# Electronic_Load_AD_V2A.net
KiCad netlist of a schematic drawn in EAGLE
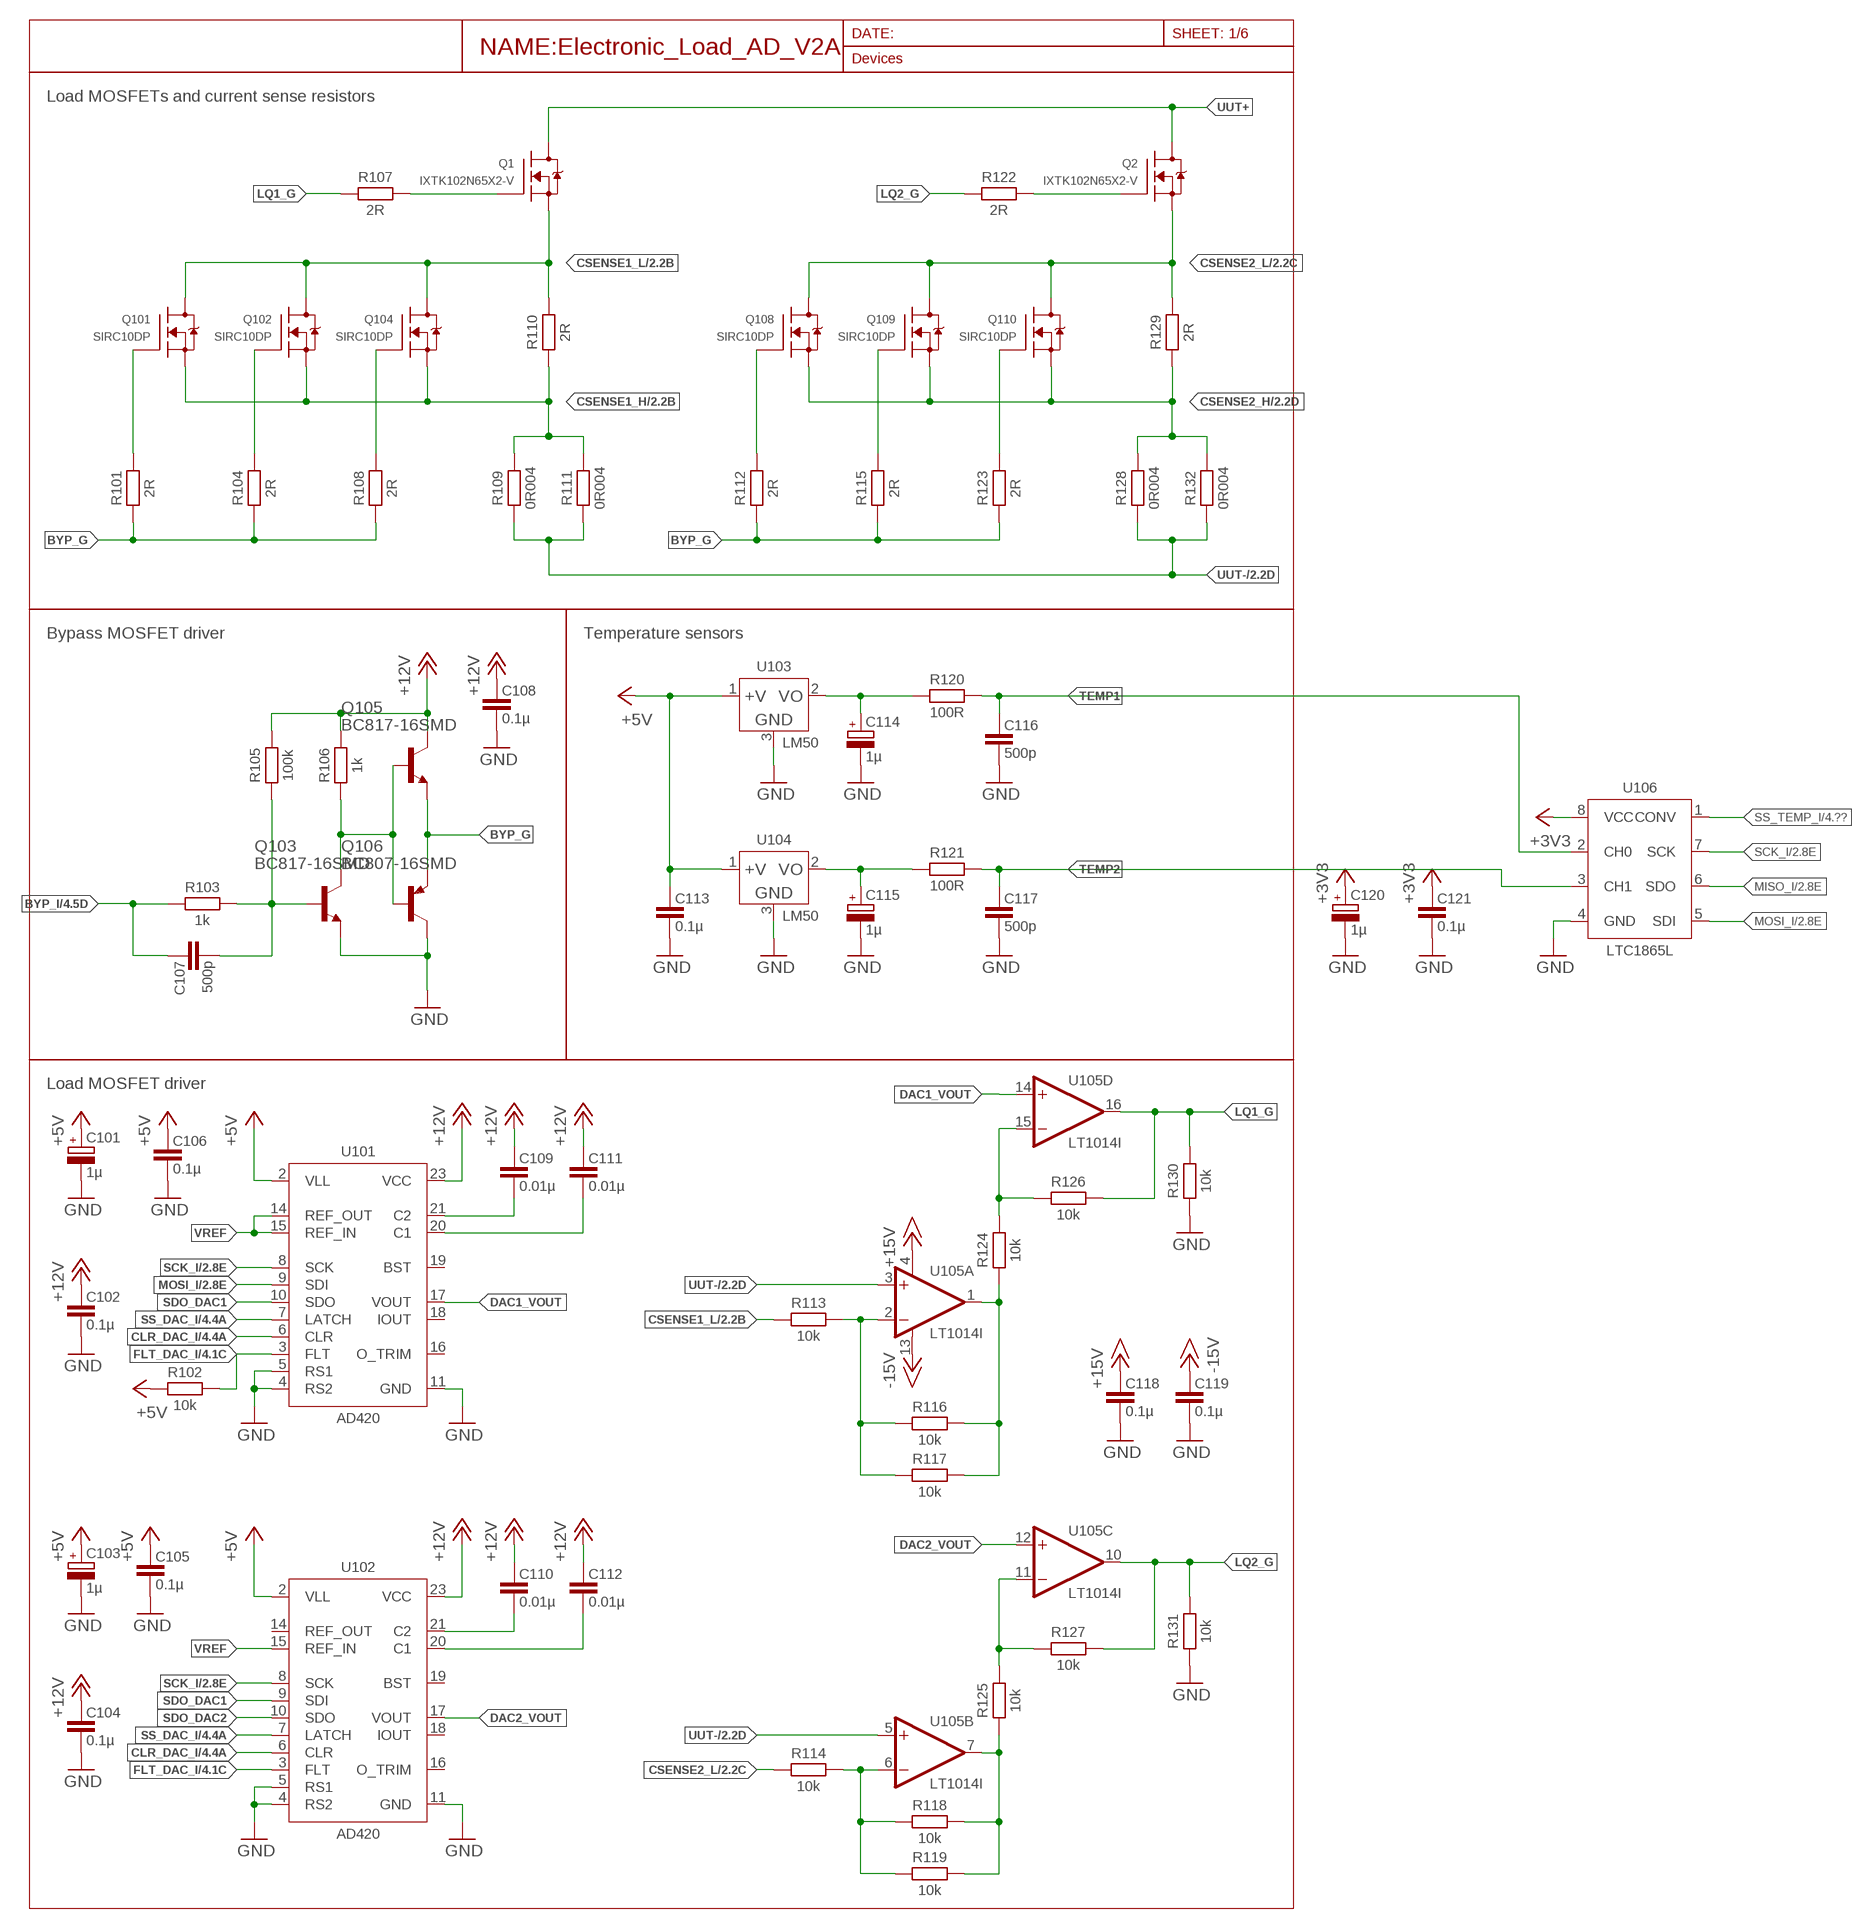
[diagram p0: schematic, sheet 1]
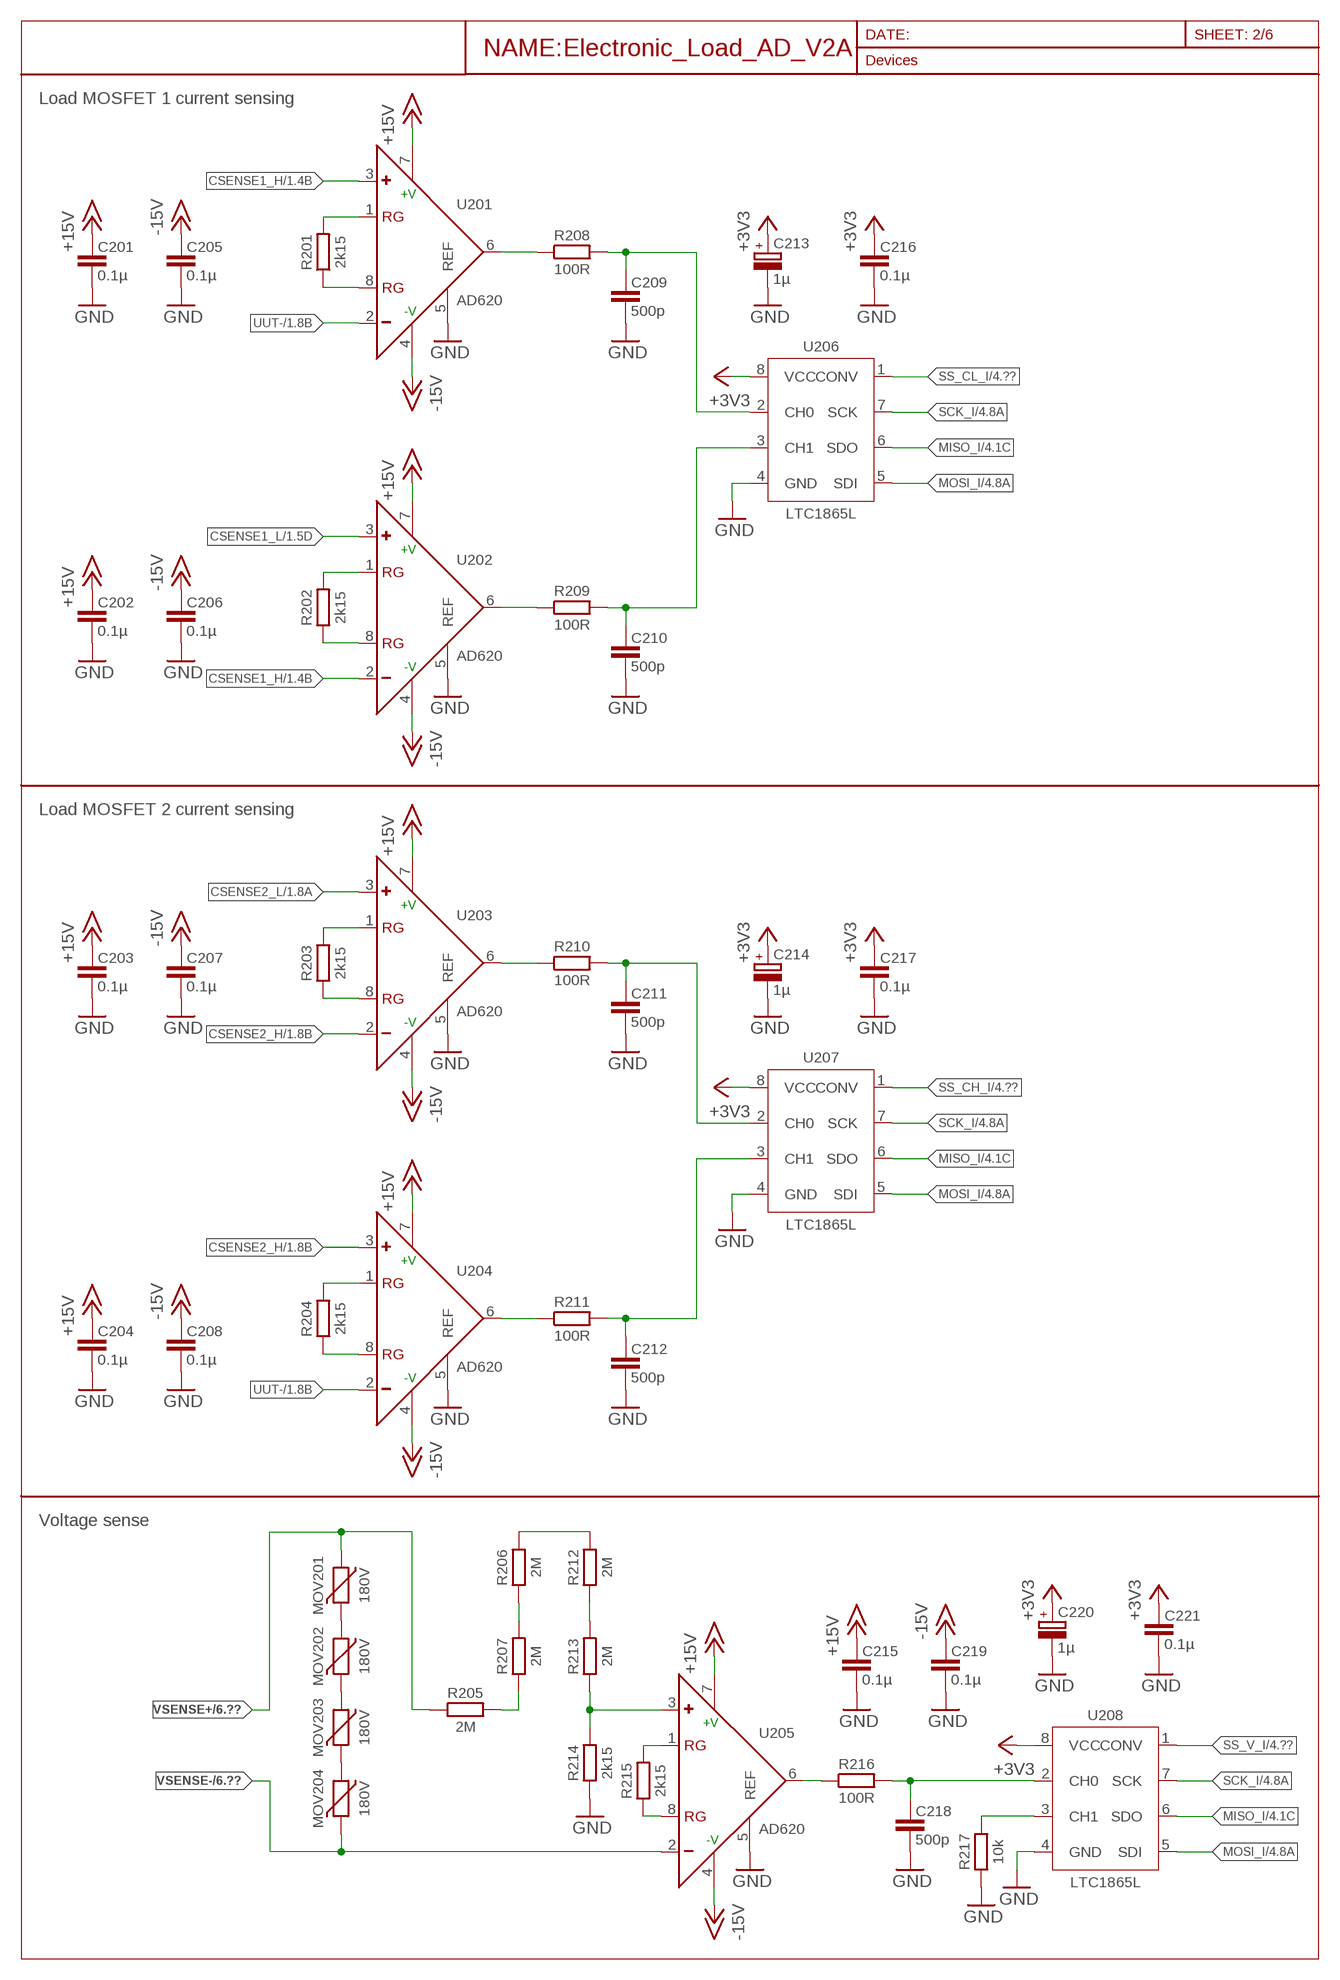
[diagram p1: schematic, sheet 2]
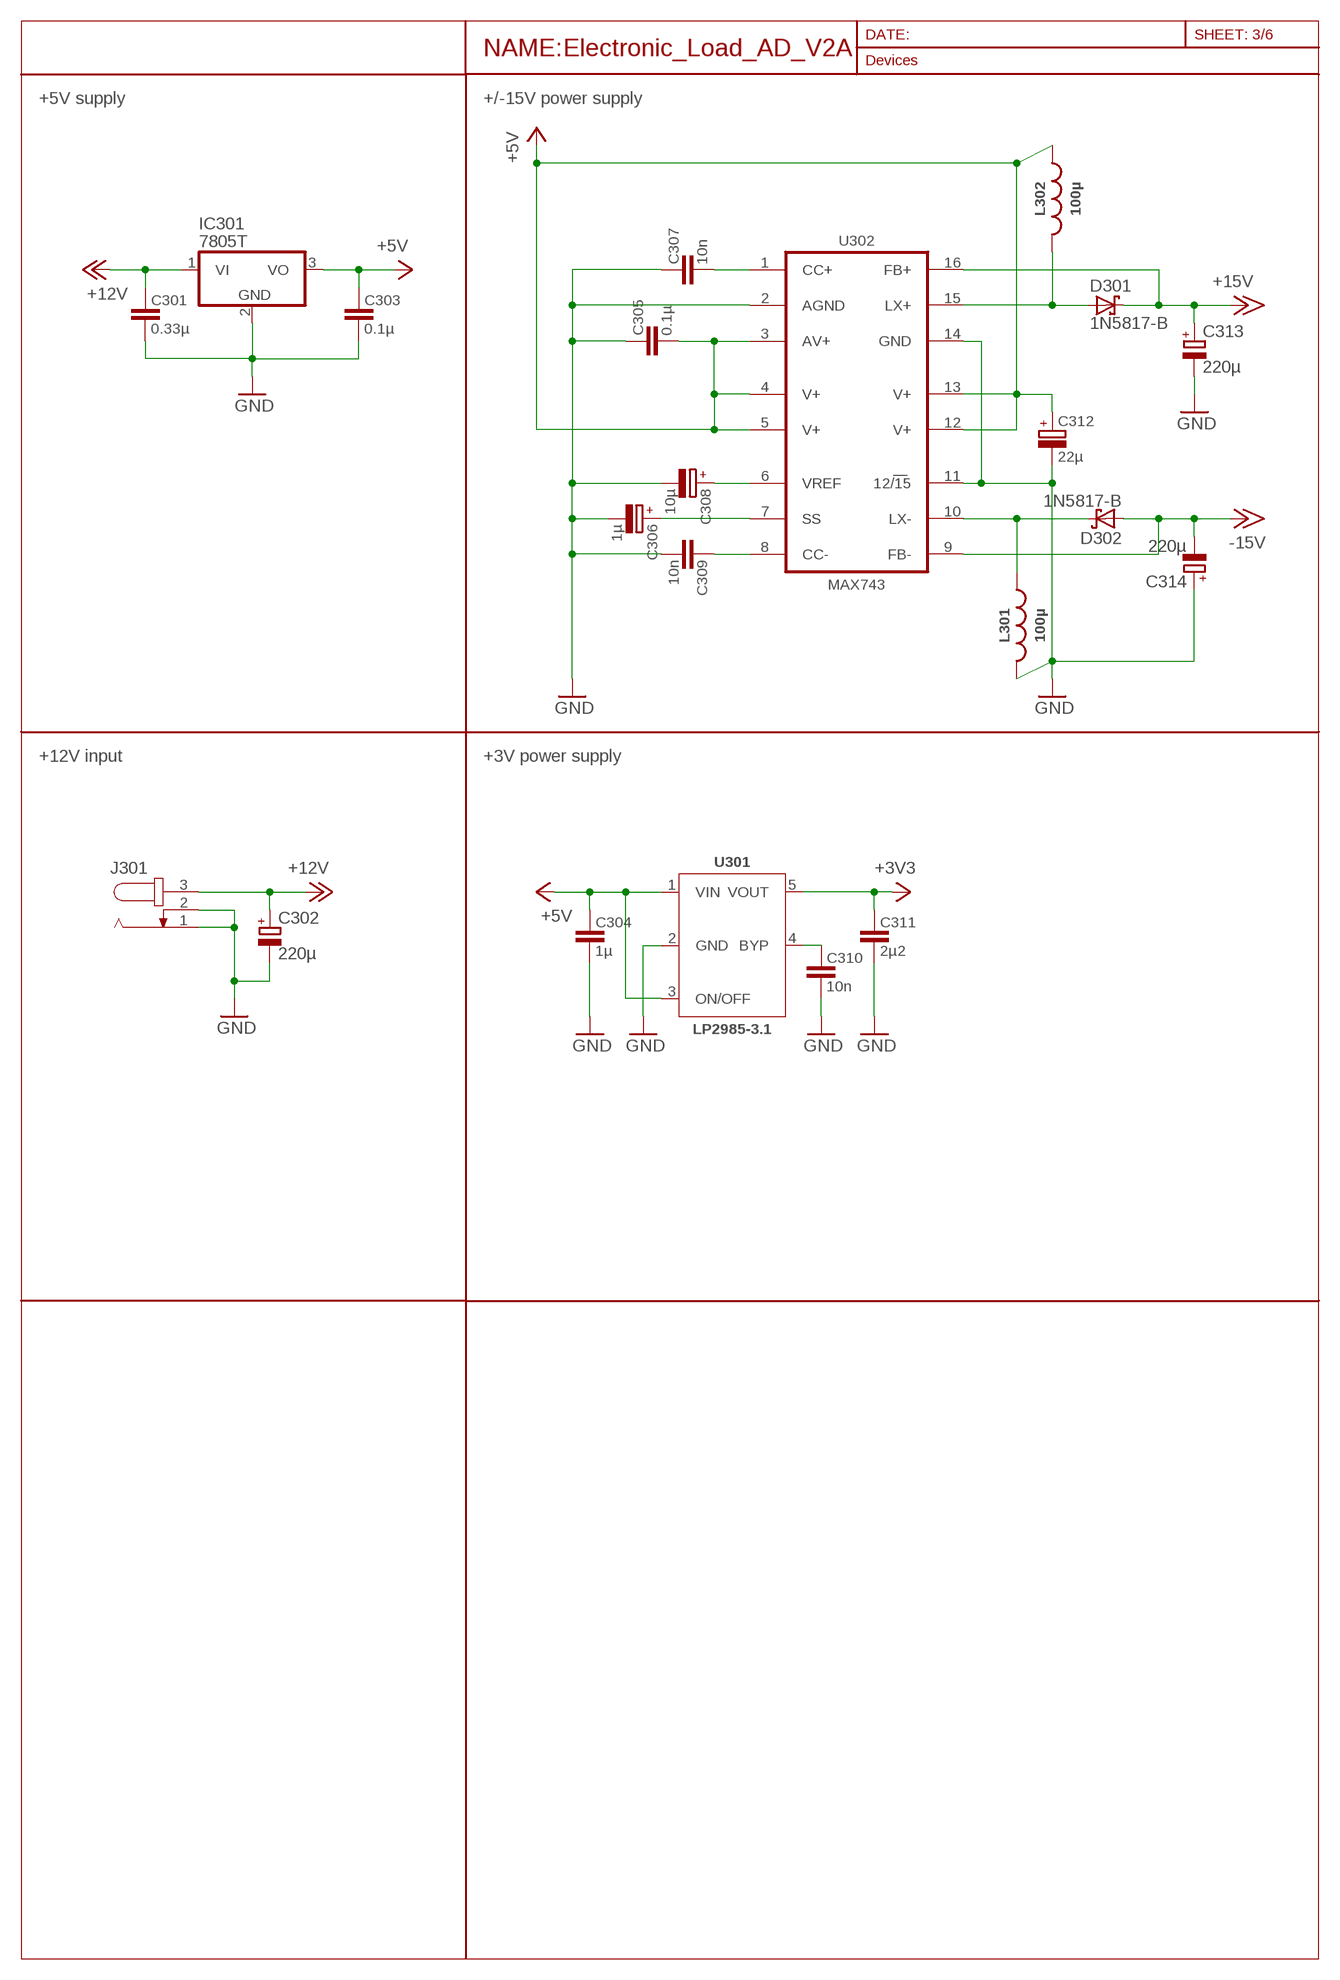
[diagram p2: schematic, sheet 3]
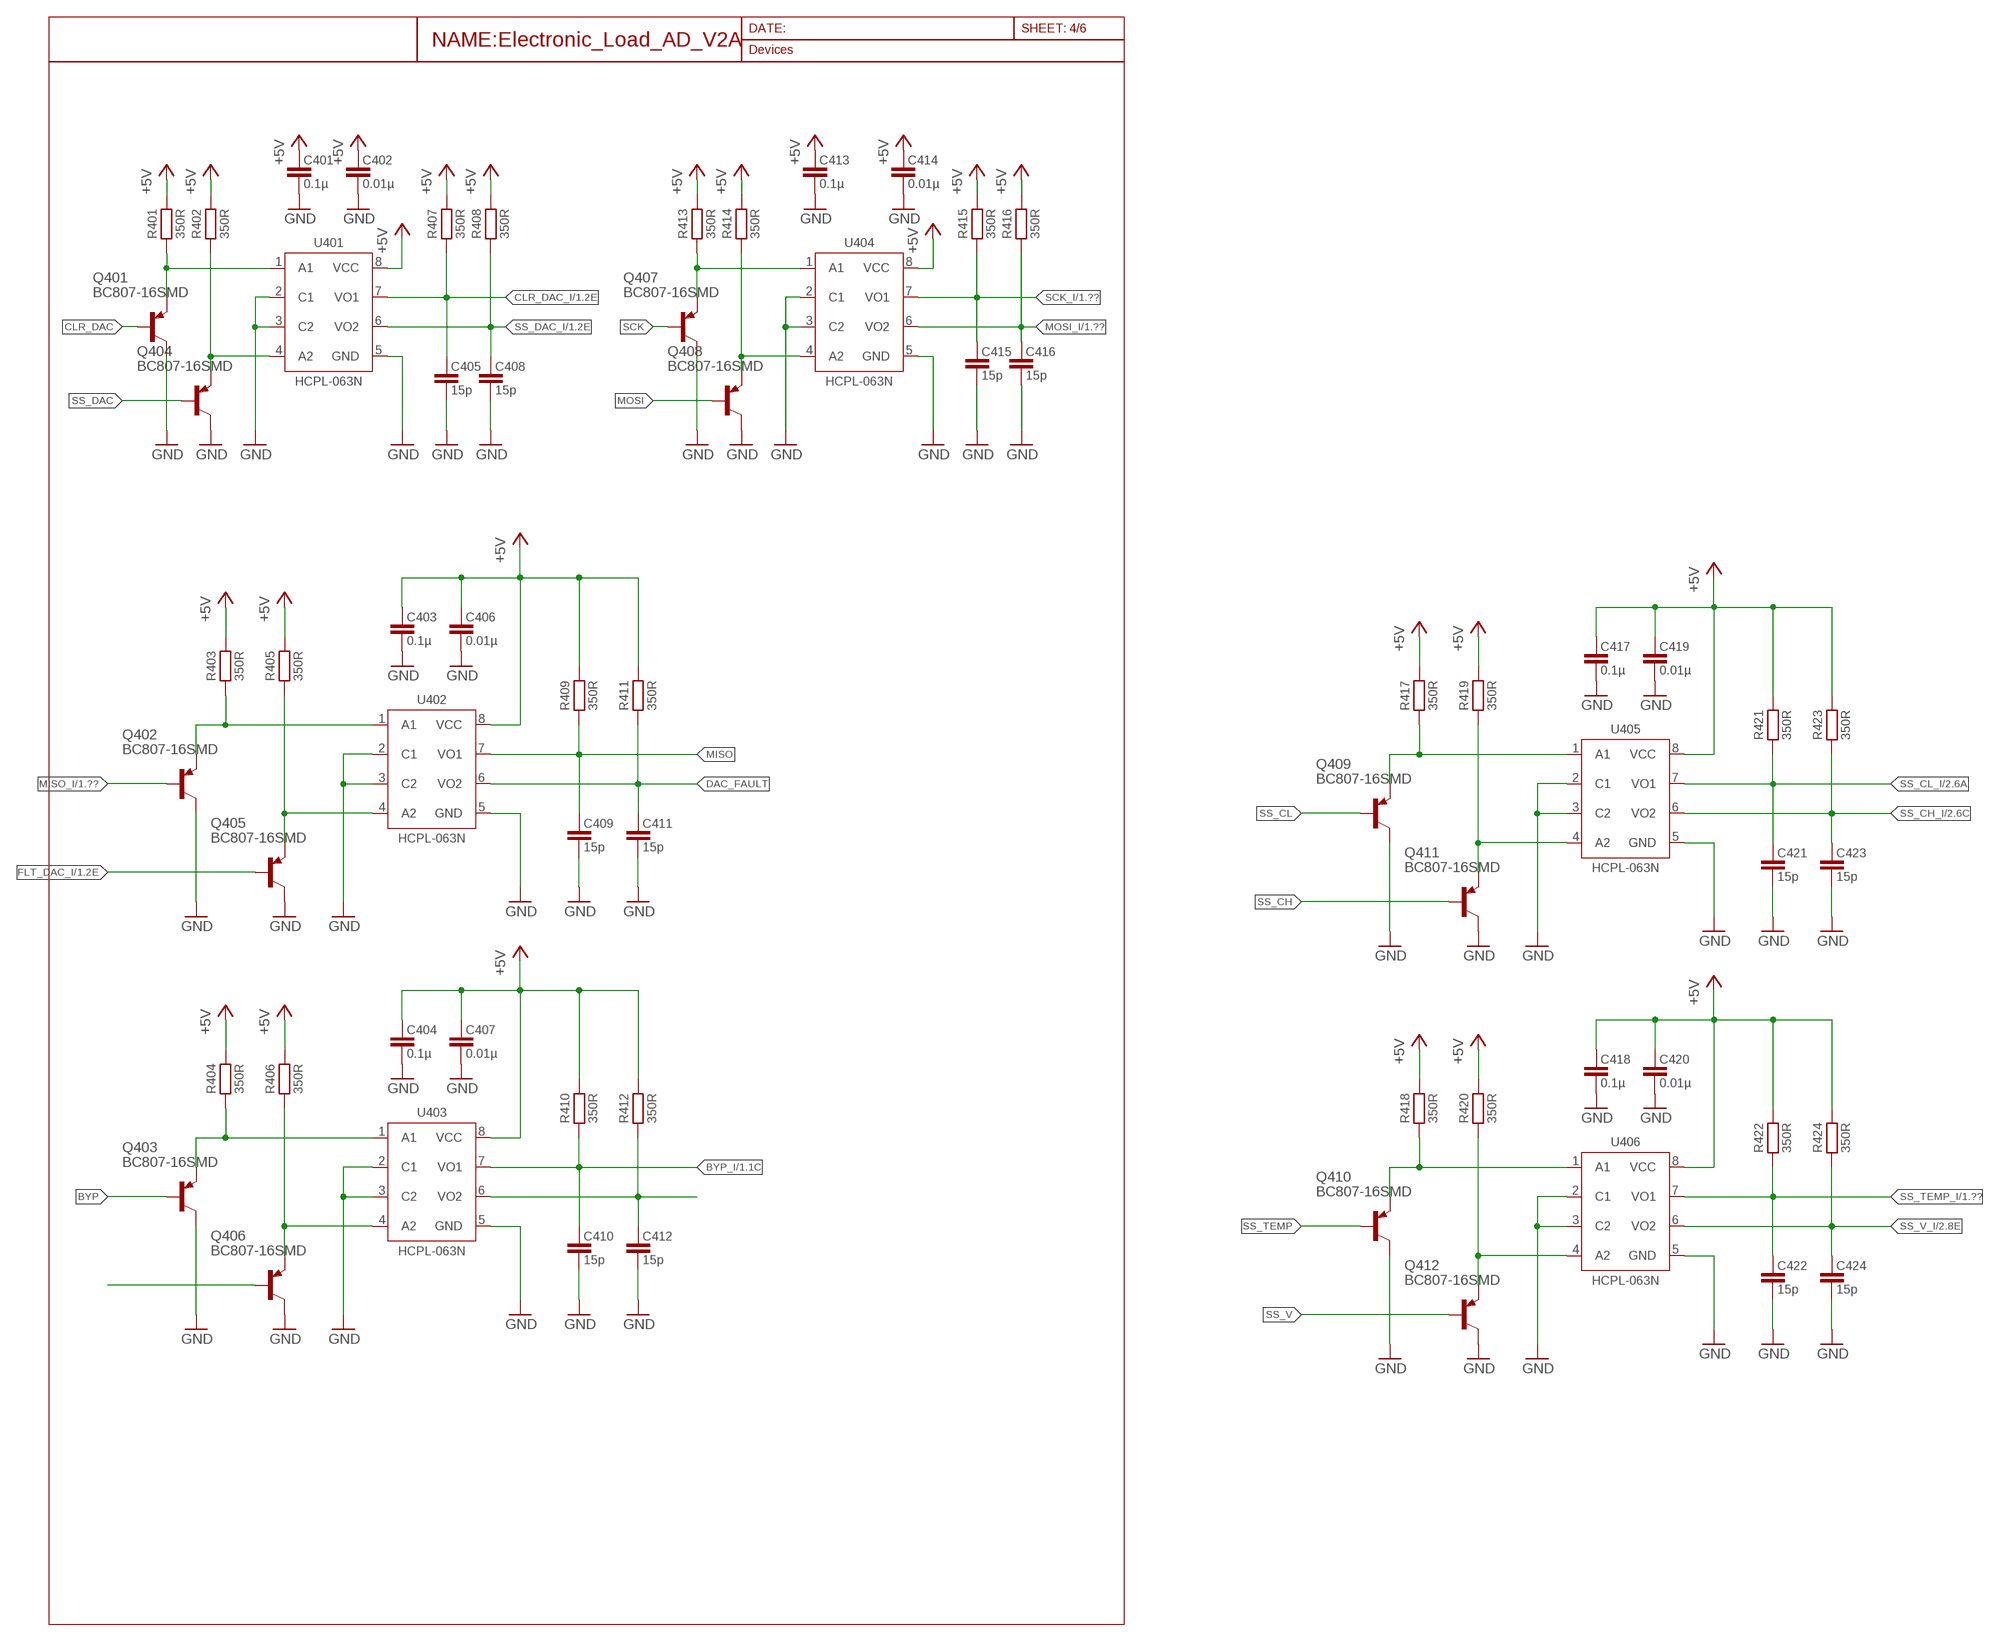
[diagram p3: schematic, sheet 4]
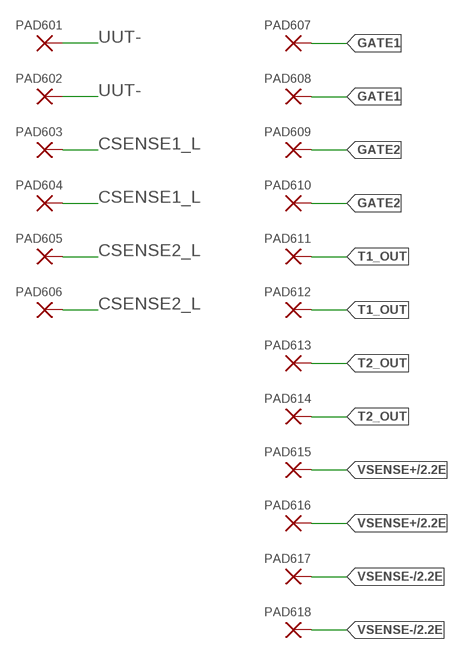
[diagram p4: schematic, sheet 6]

(export (version "E")
  (design (tool "Eeschema 10.0.6"))
  (components
    (comp (ref "C201")
      (value "0.1µ")
      (footprint "eagle-import:C3216")
      (libsource (lib "eagle-import") (part "C-EU-3216"))
    )
    (comp (ref "C202")
      (value "0.1µ")
      (footprint "eagle-import:C3216")
      (libsource (lib "eagle-import") (part "C-EU-3216"))
    )
    (comp (ref "C203")
      (value "0.1µ")
      (footprint "eagle-import:C3216")
      (libsource (lib "eagle-import") (part "C-EU-3216"))
    )
    (comp (ref "C204")
      (value "0.1µ")
      (footprint "eagle-import:C3216")
      (libsource (lib "eagle-import") (part "C-EU-3216"))
    )
    (comp (ref "C205")
      (value "0.1µ")
      (footprint "eagle-import:C3216")
      (libsource (lib "eagle-import") (part "C-EU-3216"))
    )
    (comp (ref "C206")
      (value "0.1µ")
      (footprint "eagle-import:C3216")
      (libsource (lib "eagle-import") (part "C-EU-3216"))
    )
    (comp (ref "C207")
      (value "0.1µ")
      (footprint "eagle-import:C3216")
      (libsource (lib "eagle-import") (part "C-EU-3216"))
    )
    (comp (ref "C208")
      (value "0.1µ")
      (footprint "eagle-import:C3216")
      (libsource (lib "eagle-import") (part "C-EU-3216"))
    )
    (comp (ref "C209")
      (value "500p")
      (footprint "eagle-import:C1608")
      (libsource (lib "eagle-import") (part "C-EU-1608"))
    )
    (comp (ref "C210")
      (value "500p")
      (footprint "eagle-import:C1608")
      (libsource (lib "eagle-import") (part "C-EU-1608"))
    )
    (comp (ref "C211")
      (value "500p")
      (footprint "eagle-import:C1608")
      (libsource (lib "eagle-import") (part "C-EU-1608"))
    )
    (comp (ref "C212")
      (value "500p")
      (footprint "eagle-import:C1608")
      (libsource (lib "eagle-import") (part "C-EU-1608"))
    )
    (comp (ref "C213")
      (value "1µ")
      (footprint "eagle-import:CT3216")
      (libsource (lib "eagle-import") (part "CPOL-3216-A"))
    )
    (comp (ref "C214")
      (value "1µ")
      (footprint "eagle-import:CT3216")
      (libsource (lib "eagle-import") (part "CPOL-3216-A"))
    )
    (comp (ref "C215")
      (value "0.1µ")
      (footprint "eagle-import:C3216")
      (libsource (lib "eagle-import") (part "C-EU-3216"))
    )
    (comp (ref "C216")
      (value "0.1µ")
      (footprint "eagle-import:C3216")
      (libsource (lib "eagle-import") (part "C-EU-3216"))
    )
    (comp (ref "C217")
      (value "0.1µ")
      (footprint "eagle-import:C3216")
      (libsource (lib "eagle-import") (part "C-EU-3216"))
    )
    (comp (ref "C218")
      (value "500p")
      (footprint "eagle-import:C1608")
      (libsource (lib "eagle-import") (part "C-EU-1608"))
    )
    (comp (ref "C219")
      (value "0.1µ")
      (footprint "eagle-import:C3216")
      (libsource (lib "eagle-import") (part "C-EU-3216"))
    )
    (comp (ref "C220")
      (value "1µ")
      (footprint "eagle-import:CT3216")
      (libsource (lib "eagle-import") (part "CPOL-3216-A"))
    )
    (comp (ref "C221")
      (value "0.1µ")
      (footprint "eagle-import:C3216")
      (libsource (lib "eagle-import") (part "C-EU-3216"))
    )
    (comp (ref "MOV201")
      (value "180V")
      (footprint "eagle-import:R3225W")
      (libsource (lib "eagle-import") (part "MOV-3225"))
    )
    (comp (ref "MOV202")
      (value "180V")
      (footprint "eagle-import:R3225W")
      (libsource (lib "eagle-import") (part "MOV-3225"))
    )
    (comp (ref "MOV203")
      (value "180V")
      (footprint "eagle-import:R3225W")
      (libsource (lib "eagle-import") (part "MOV-3225"))
    )
    (comp (ref "MOV204")
      (value "180V")
      (footprint "eagle-import:R3225W")
      (libsource (lib "eagle-import") (part "MOV-3225"))
    )
    (comp (ref "R201")
      (value "2k15")
      (footprint "eagle-import:R2012W")
      (libsource (lib "eagle-import") (part "R-EU-2012"))
    )
    (comp (ref "R202")
      (value "2k15")
      (footprint "eagle-import:R2012W")
      (libsource (lib "eagle-import") (part "R-EU-2012"))
    )
    (comp (ref "R203")
      (value "2k15")
      (footprint "eagle-import:R2012W")
      (libsource (lib "eagle-import") (part "R-EU-2012"))
    )
    (comp (ref "R204")
      (value "2k15")
      (footprint "eagle-import:R2012W")
      (libsource (lib "eagle-import") (part "R-EU-2012"))
    )
    (comp (ref "R205")
      (value "2M")
      (footprint "eagle-import:R3216W")
      (libsource (lib "eagle-import") (part "R-EU-3216"))
    )
    (comp (ref "R206")
      (value "2M")
      (footprint "eagle-import:R3216W")
      (libsource (lib "eagle-import") (part "R-EU-3216"))
    )
    (comp (ref "R207")
      (value "2M")
      (footprint "eagle-import:R3216W")
      (libsource (lib "eagle-import") (part "R-EU-3216"))
    )
    (comp (ref "R208")
      (value "100R")
      (footprint "eagle-import:R2012W")
      (libsource (lib "eagle-import") (part "R-EU-2012"))
    )
    (comp (ref "R209")
      (value "100R")
      (footprint "eagle-import:R2012W")
      (libsource (lib "eagle-import") (part "R-EU-2012"))
    )
    (comp (ref "R210")
      (value "100R")
      (footprint "eagle-import:R2012W")
      (libsource (lib "eagle-import") (part "R-EU-2012"))
    )
    (comp (ref "R211")
      (value "100R")
      (footprint "eagle-import:R2012W")
      (libsource (lib "eagle-import") (part "R-EU-2012"))
    )
    (comp (ref "R212")
      (value "2M")
      (footprint "eagle-import:R3216W")
      (libsource (lib "eagle-import") (part "R-EU-3216"))
    )
    (comp (ref "R213")
      (value "2M")
      (footprint "eagle-import:R3216W")
      (libsource (lib "eagle-import") (part "R-EU-3216"))
    )
    (comp (ref "R214")
      (value "2k15")
      (footprint "eagle-import:R2012W")
      (libsource (lib "eagle-import") (part "R-EU-2012"))
    )
    (comp (ref "R215")
      (value "2k15")
      (footprint "eagle-import:R2012W")
      (libsource (lib "eagle-import") (part "R-EU-2012"))
    )
    (comp (ref "R216")
      (value "100R")
      (footprint "eagle-import:R2012W")
      (libsource (lib "eagle-import") (part "R-EU-2012"))
    )
    (comp (ref "R217")
      (value "10k")
      (footprint "eagle-import:R1608")
      (libsource (lib "eagle-import") (part "R-EU-1608"))
    )
    (comp (ref "U201")
      (value "AD620")
      (footprint "eagle-import:SO8")
      (libsource (lib "eagle-import") (part "AD620R-8"))
    )
    (comp (ref "U202")
      (value "AD620")
      (footprint "eagle-import:SO8")
      (libsource (lib "eagle-import") (part "AD620R-8"))
    )
    (comp (ref "U203")
      (value "AD620")
      (footprint "eagle-import:SO8")
      (libsource (lib "eagle-import") (part "AD620R-8"))
    )
    (comp (ref "U204")
      (value "AD620")
      (footprint "eagle-import:SO8")
      (libsource (lib "eagle-import") (part "AD620R-8"))
    )
    (comp (ref "U205")
      (value "AD620")
      (footprint "eagle-import:SO8")
      (libsource (lib "eagle-import") (part "AD620R-8"))
    )
    (comp (ref "U206")
      (value "LTC1865L")
      (footprint "eagle-import:SO8")
      (libsource (lib "eagle-import") (part "LTC1865L"))
    )
    (comp (ref "U207")
      (value "LTC1865L")
      (footprint "eagle-import:SO8")
      (libsource (lib "eagle-import") (part "LTC1865L"))
    )
    (comp (ref "U208")
      (value "LTC1865L")
      (footprint "eagle-import:SO8")
      (libsource (lib "eagle-import") (part "LTC1865L"))
    )
    (comp (ref "C301")
      (value "0.33µ")
      (footprint "eagle-import:C3216")
      (libsource (lib "eagle-import") (part "C-EU-3216"))
    )
    (comp (ref "C302")
      (value "220µ")
      (footprint "eagle-import:E3,5-10")
      (libsource (lib "eagle-import") (part "CPOL-EUE3.5-10"))
    )
    (comp (ref "C303")
      (value "0.1µ")
      (footprint "eagle-import:C3216")
      (libsource (lib "eagle-import") (part "C-EU-3216"))
    )
    (comp (ref "C304")
      (value "1µ")
      (footprint "eagle-import:C3216")
      (libsource (lib "eagle-import") (part "C-EU-3216"))
    )
    (comp (ref "C305")
      (value "0.1µ")
      (footprint "eagle-import:C3216")
      (libsource (lib "eagle-import") (part "C-EU-3216"))
    )
    (comp (ref "C306")
      (value "1µ")
      (footprint "eagle-import:CT3216")
      (libsource (lib "eagle-import") (part "CPOL-3216-A"))
    )
    (comp (ref "C307")
      (value "10n")
      (footprint "eagle-import:C3216")
      (libsource (lib "eagle-import") (part "C-EU-3216"))
    )
    (comp (ref "C308")
      (value "10µ")
      (footprint "eagle-import:CT6032")
      (libsource (lib "eagle-import") (part "CPOL-6032-C"))
    )
    (comp (ref "C309")
      (value "10n")
      (footprint "eagle-import:C3216")
      (libsource (lib "eagle-import") (part "C-EU-3216"))
    )
    (comp (ref "C310")
      (value "10n")
      (footprint "eagle-import:C3216")
      (libsource (lib "eagle-import") (part "C-EU-3216"))
    )
    (comp (ref "C311")
      (value "2µ2")
      (footprint "eagle-import:C3216")
      (libsource (lib "eagle-import") (part "C-EU-3216"))
    )
    (comp (ref "C312")
      (value "22µ")
      (footprint "eagle-import:CT6032")
      (libsource (lib "eagle-import") (part "CPOL-6032-C"))
    )
    (comp (ref "C313")
      (value "220µ")
      (footprint "eagle-import:E3,5-10")
      (libsource (lib "eagle-import") (part "CPOL-EUE3.5-10"))
    )
    (comp (ref "C314")
      (value "220µ")
      (footprint "eagle-import:E3,5-10")
      (libsource (lib "eagle-import") (part "CPOL-EUE3.5-10"))
    )
    (comp (ref "D301")
      (value "1N5817-B")
      (footprint "eagle-import:DO41-7.6")
      (libsource (lib "eagle-import") (part "1N5817-B"))
    )
    (comp (ref "D302")
      (value "1N5817-B")
      (footprint "eagle-import:DO41-7.6")
      (libsource (lib "eagle-import") (part "1N5817-B"))
    )
    (comp (ref "IC301")
      (value "7805T")
      (footprint "eagle-import:TO220H")
      (libsource (lib "eagle-import") (part "78T05"))
    )
    (comp (ref "J301")
      (value "JACK-PLUG0")
      (footprint "eagle-import:SPC4077")
      (libsource (lib "eagle-import") (part "JACK-PLUG0"))
    )
    (comp (ref "L301")
      (value "100µ")
      (footprint "eagle-import:SRN1060")
      (libsource (lib "eagle-import") (part "L-EUSRN1060"))
    )
    (comp (ref "L302")
      (value "100µ")
      (footprint "eagle-import:SRN1060")
      (libsource (lib "eagle-import") (part "L-EUSRN1060"))
    )
    (comp (ref "U301")
      (value "LP2985-3.1")
      (footprint "eagle-import:SOT23-5L")
      (libsource (lib "eagle-import") (part "LP2985-3.1"))
    )
    (comp (ref "U302")
      (value "MAX743")
      (footprint "eagle-import:SO16W")
      (libsource (lib "eagle-import") (part "MAX743WE"))
    )
    (comp (ref "C401")
      (value "0.1µ")
      (footprint "eagle-import:C3216")
      (libsource (lib "eagle-import") (part "C-EU-3216"))
    )
    (comp (ref "C402")
      (value "0.01µ")
      (footprint "eagle-import:C3216")
      (libsource (lib "eagle-import") (part "C-EU-3216"))
    )
    (comp (ref "C403")
      (value "0.1µ")
      (footprint "eagle-import:C3216")
      (libsource (lib "eagle-import") (part "C-EU-3216"))
    )
    (comp (ref "C404")
      (value "0.1µ")
      (footprint "eagle-import:C3216")
      (libsource (lib "eagle-import") (part "C-EU-3216"))
    )
    (comp (ref "C405")
      (value "15p")
      (footprint "eagle-import:C1608")
      (libsource (lib "eagle-import") (part "C-EU-1608"))
    )
    (comp (ref "C406")
      (value "0.01µ")
      (footprint "eagle-import:C3216")
      (libsource (lib "eagle-import") (part "C-EU-3216"))
    )
    (comp (ref "C407")
      (value "0.01µ")
      (footprint "eagle-import:C3216")
      (libsource (lib "eagle-import") (part "C-EU-3216"))
    )
    (comp (ref "C408")
      (value "15p")
      (footprint "eagle-import:C1608")
      (libsource (lib "eagle-import") (part "C-EU-1608"))
    )
    (comp (ref "C409")
      (value "15p")
      (footprint "eagle-import:C1608")
      (libsource (lib "eagle-import") (part "C-EU-1608"))
    )
    (comp (ref "C410")
      (value "15p")
      (footprint "eagle-import:C1608")
      (libsource (lib "eagle-import") (part "C-EU-1608"))
    )
    (comp (ref "C411")
      (value "15p")
      (footprint "eagle-import:C1608")
      (libsource (lib "eagle-import") (part "C-EU-1608"))
    )
    (comp (ref "C412")
      (value "15p")
      (footprint "eagle-import:C1608")
      (libsource (lib "eagle-import") (part "C-EU-1608"))
    )
    (comp (ref "C413")
      (value "0.1µ")
      (footprint "eagle-import:C3216")
      (libsource (lib "eagle-import") (part "C-EU-3216"))
    )
    (comp (ref "C414")
      (value "0.01µ")
      (footprint "eagle-import:C3216")
      (libsource (lib "eagle-import") (part "C-EU-3216"))
    )
    (comp (ref "C415")
      (value "15p")
      (footprint "eagle-import:C1608")
      (libsource (lib "eagle-import") (part "C-EU-1608"))
    )
    (comp (ref "C416")
      (value "15p")
      (footprint "eagle-import:C1608")
      (libsource (lib "eagle-import") (part "C-EU-1608"))
    )
    (comp (ref "C417")
      (value "0.1µ")
      (footprint "eagle-import:C3216")
      (libsource (lib "eagle-import") (part "C-EU-3216"))
    )
    (comp (ref "C418")
      (value "0.1µ")
      (footprint "eagle-import:C3216")
      (libsource (lib "eagle-import") (part "C-EU-3216"))
    )
    (comp (ref "C419")
      (value "0.01µ")
      (footprint "eagle-import:C3216")
      (libsource (lib "eagle-import") (part "C-EU-3216"))
    )
    (comp (ref "C420")
      (value "0.01µ")
      (footprint "eagle-import:C3216")
      (libsource (lib "eagle-import") (part "C-EU-3216"))
    )
    (comp (ref "C421")
      (value "15p")
      (footprint "eagle-import:C1608")
      (libsource (lib "eagle-import") (part "C-EU-1608"))
    )
    (comp (ref "C422")
      (value "15p")
      (footprint "eagle-import:C1608")
      (libsource (lib "eagle-import") (part "C-EU-1608"))
    )
    (comp (ref "C423")
      (value "15p")
      (footprint "eagle-import:C1608")
      (libsource (lib "eagle-import") (part "C-EU-1608"))
    )
    (comp (ref "C424")
      (value "15p")
      (footprint "eagle-import:C1608")
      (libsource (lib "eagle-import") (part "C-EU-1608"))
    )
    (comp (ref "Q401")
      (value "BC807-16SMD")
      (footprint "eagle-import:SOT23-BEC")
      (libsource (lib "eagle-import") (part "BC807SMD-16"))
    )
    (comp (ref "Q402")
      (value "BC807-16SMD")
      (footprint "eagle-import:SOT23-BEC")
      (libsource (lib "eagle-import") (part "BC807SMD-16"))
    )
    (comp (ref "Q403")
      (value "BC807-16SMD")
      (footprint "eagle-import:SOT23-BEC")
      (libsource (lib "eagle-import") (part "BC807SMD-16"))
    )
    (comp (ref "Q404")
      (value "BC807-16SMD")
      (footprint "eagle-import:SOT23-BEC")
      (libsource (lib "eagle-import") (part "BC807SMD-16"))
    )
    (comp (ref "Q405")
      (value "BC807-16SMD")
      (footprint "eagle-import:SOT23-BEC")
      (libsource (lib "eagle-import") (part "BC807SMD-16"))
    )
    (comp (ref "Q406")
      (value "BC807-16SMD")
      (footprint "eagle-import:SOT23-BEC")
      (libsource (lib "eagle-import") (part "BC807SMD-16"))
    )
    (comp (ref "Q407")
      (value "BC807-16SMD")
      (footprint "eagle-import:SOT23-BEC")
      (libsource (lib "eagle-import") (part "BC807SMD-16"))
    )
    (comp (ref "Q408")
      (value "BC807-16SMD")
      (footprint "eagle-import:SOT23-BEC")
      (libsource (lib "eagle-import") (part "BC807SMD-16"))
    )
    (comp (ref "Q409")
      (value "BC807-16SMD")
      (footprint "eagle-import:SOT23-BEC")
      (libsource (lib "eagle-import") (part "BC807SMD-16"))
    )
    (comp (ref "Q410")
      (value "BC807-16SMD")
      (footprint "eagle-import:SOT23-BEC")
      (libsource (lib "eagle-import") (part "BC807SMD-16"))
    )
    (comp (ref "Q411")
      (value "BC807-16SMD")
      (footprint "eagle-import:SOT23-BEC")
      (libsource (lib "eagle-import") (part "BC807SMD-16"))
    )
    (comp (ref "Q412")
      (value "BC807-16SMD")
      (footprint "eagle-import:SOT23-BEC")
      (libsource (lib "eagle-import") (part "BC807SMD-16"))
    )
    (comp (ref "R401")
      (value "350R")
      (footprint "eagle-import:R1608")
      (libsource (lib "eagle-import") (part "R-EU-1608"))
    )
    (comp (ref "R402")
      (value "350R")
      (footprint "eagle-import:R1608")
      (libsource (lib "eagle-import") (part "R-EU-1608"))
    )
    (comp (ref "R403")
      (value "350R")
      (footprint "eagle-import:R1608")
      (libsource (lib "eagle-import") (part "R-EU-1608"))
    )
    (comp (ref "R404")
      (value "350R")
      (footprint "eagle-import:R1608")
      (libsource (lib "eagle-import") (part "R-EU-1608"))
    )
    (comp (ref "R405")
      (value "350R")
      (footprint "eagle-import:R1608")
      (libsource (lib "eagle-import") (part "R-EU-1608"))
    )
    (comp (ref "R406")
      (value "350R")
      (footprint "eagle-import:R1608")
      (libsource (lib "eagle-import") (part "R-EU-1608"))
    )
    (comp (ref "R407")
      (value "350R")
      (footprint "eagle-import:R1608")
      (libsource (lib "eagle-import") (part "R-EU-1608"))
    )
    (comp (ref "R408")
      (value "350R")
      (footprint "eagle-import:R1608")
      (libsource (lib "eagle-import") (part "R-EU-1608"))
    )
    (comp (ref "R409")
      (value "350R")
      (footprint "eagle-import:R1608")
      (libsource (lib "eagle-import") (part "R-EU-1608"))
    )
    (comp (ref "R410")
      (value "350R")
      (footprint "eagle-import:R1608")
      (libsource (lib "eagle-import") (part "R-EU-1608"))
    )
    (comp (ref "R411")
      (value "350R")
      (footprint "eagle-import:R1608")
      (libsource (lib "eagle-import") (part "R-EU-1608"))
    )
    (comp (ref "R412")
      (value "350R")
      (footprint "eagle-import:R1608")
      (libsource (lib "eagle-import") (part "R-EU-1608"))
    )
    (comp (ref "R413")
      (value "350R")
      (footprint "eagle-import:R1608")
      (libsource (lib "eagle-import") (part "R-EU-1608"))
    )
    (comp (ref "R414")
      (value "350R")
      (footprint "eagle-import:R1608")
      (libsource (lib "eagle-import") (part "R-EU-1608"))
    )
    (comp (ref "R415")
      (value "350R")
      (footprint "eagle-import:R1608")
      (libsource (lib "eagle-import") (part "R-EU-1608"))
    )
    (comp (ref "R416")
      (value "350R")
      (footprint "eagle-import:R1608")
      (libsource (lib "eagle-import") (part "R-EU-1608"))
    )
    (comp (ref "R417")
      (value "350R")
      (footprint "eagle-import:R1608")
      (libsource (lib "eagle-import") (part "R-EU-1608"))
    )
    (comp (ref "R418")
      (value "350R")
      (footprint "eagle-import:R1608")
      (libsource (lib "eagle-import") (part "R-EU-1608"))
    )
    (comp (ref "R419")
      (value "350R")
      (footprint "eagle-import:R1608")
      (libsource (lib "eagle-import") (part "R-EU-1608"))
    )
    (comp (ref "R420")
      (value "350R")
      (footprint "eagle-import:R1608")
      (libsource (lib "eagle-import") (part "R-EU-1608"))
    )
    (comp (ref "R421")
      (value "350R")
      (footprint "eagle-import:R1608")
      (libsource (lib "eagle-import") (part "R-EU-1608"))
    )
    (comp (ref "R422")
      (value "350R")
      (footprint "eagle-import:R1608")
      (libsource (lib "eagle-import") (part "R-EU-1608"))
    )
    (comp (ref "R423")
      (value "350R")
      (footprint "eagle-import:R1608")
      (libsource (lib "eagle-import") (part "R-EU-1608"))
    )
    (comp (ref "R424")
      (value "350R")
      (footprint "eagle-import:R1608")
      (libsource (lib "eagle-import") (part "R-EU-1608"))
    )
    (comp (ref "U401")
      (value "HCPL-063N")
      (footprint "eagle-import:SO8")
      (libsource (lib "eagle-import") (part "HCPL-063N"))
    )
    (comp (ref "U402")
      (value "HCPL-063N")
      (footprint "eagle-import:SO8")
      (libsource (lib "eagle-import") (part "HCPL-063N"))
    )
    (comp (ref "U403")
      (value "HCPL-063N")
      (footprint "eagle-import:SO8")
      (libsource (lib "eagle-import") (part "HCPL-063N"))
    )
    (comp (ref "U404")
      (value "HCPL-063N")
      (footprint "eagle-import:SO8")
      (libsource (lib "eagle-import") (part "HCPL-063N"))
    )
    (comp (ref "U405")
      (value "HCPL-063N")
      (footprint "eagle-import:SO8")
      (libsource (lib "eagle-import") (part "HCPL-063N"))
    )
    (comp (ref "U406")
      (value "HCPL-063N")
      (footprint "eagle-import:SO8")
      (libsource (lib "eagle-import") (part "HCPL-063N"))
    )
    (comp (ref "PAD601")
      (value "PAD-10X4")
      (footprint "eagle-import:PAD-10X4")
      (libsource (lib "eagle-import") (part "PAD-10X4"))
    )
    (comp (ref "PAD602")
      (value "PAD-10X4")
      (footprint "eagle-import:PAD-10X4")
      (libsource (lib "eagle-import") (part "PAD-10X4"))
    )
    (comp (ref "PAD603")
      (value "PAD-10X4")
      (footprint "eagle-import:PAD-10X4")
      (libsource (lib "eagle-import") (part "PAD-10X4"))
    )
    (comp (ref "PAD604")
      (value "PAD-10X4")
      (footprint "eagle-import:PAD-10X4")
      (libsource (lib "eagle-import") (part "PAD-10X4"))
    )
    (comp (ref "PAD605")
      (value "PAD-10X4")
      (footprint "eagle-import:PAD-10X4")
      (libsource (lib "eagle-import") (part "PAD-10X4"))
    )
    (comp (ref "PAD606")
      (value "PAD-10X4")
      (footprint "eagle-import:PAD-10X4")
      (libsource (lib "eagle-import") (part "PAD-10X4"))
    )
    (comp (ref "PAD607")
      (value "PAD-5X2")
      (footprint "eagle-import:PAD-5X2")
      (libsource (lib "eagle-import") (part "PAD-5X2"))
    )
    (comp (ref "PAD608")
      (value "PAD-5X2")
      (footprint "eagle-import:PAD-5X2")
      (libsource (lib "eagle-import") (part "PAD-5X2"))
    )
    (comp (ref "PAD609")
      (value "PAD-5X2")
      (footprint "eagle-import:PAD-5X2")
      (libsource (lib "eagle-import") (part "PAD-5X2"))
    )
    (comp (ref "PAD610")
      (value "PAD-5X2")
      (footprint "eagle-import:PAD-5X2")
      (libsource (lib "eagle-import") (part "PAD-5X2"))
    )
    (comp (ref "PAD611")
      (value "PAD-5X2")
      (footprint "eagle-import:PAD-5X2")
      (libsource (lib "eagle-import") (part "PAD-5X2"))
    )
    (comp (ref "PAD612")
      (value "PAD-5X2")
      (footprint "eagle-import:PAD-5X2")
      (libsource (lib "eagle-import") (part "PAD-5X2"))
    )
    (comp (ref "PAD613")
      (value "PAD-5X2")
      (footprint "eagle-import:PAD-5X2")
      (libsource (lib "eagle-import") (part "PAD-5X2"))
    )
    (comp (ref "PAD614")
      (value "PAD-5X2")
      (footprint "eagle-import:PAD-5X2")
      (libsource (lib "eagle-import") (part "PAD-5X2"))
    )
    (comp (ref "PAD615")
      (value "PAD-5X2")
      (footprint "eagle-import:PAD-5X2")
      (libsource (lib "eagle-import") (part "PAD-5X2"))
    )
    (comp (ref "PAD616")
      (value "PAD-5X2")
      (footprint "eagle-import:PAD-5X2")
      (libsource (lib "eagle-import") (part "PAD-5X2"))
    )
    (comp (ref "PAD617")
      (value "PAD-5X2")
      (footprint "eagle-import:PAD-5X2")
      (libsource (lib "eagle-import") (part "PAD-5X2"))
    )
    (comp (ref "PAD618")
      (value "PAD-5X2")
      (footprint "eagle-import:PAD-5X2")
      (libsource (lib "eagle-import") (part "PAD-5X2"))
    )
    (comp (ref "C101")
      (value "1µ")
      (footprint "eagle-import:CT3216")
      (libsource (lib "eagle-import") (part "CPOL-3216-A"))
    )
    (comp (ref "C102")
      (value "0.1µ")
      (footprint "eagle-import:C3216")
      (libsource (lib "eagle-import") (part "C-EU-3216"))
    )
    (comp (ref "C103")
      (value "1µ")
      (footprint "eagle-import:CT3216")
      (libsource (lib "eagle-import") (part "CPOL-3216-A"))
    )
    (comp (ref "C104")
      (value "0.1µ")
      (footprint "eagle-import:C3216")
      (libsource (lib "eagle-import") (part "C-EU-3216"))
    )
    (comp (ref "C105")
      (value "0.1µ")
      (footprint "eagle-import:C3216")
      (libsource (lib "eagle-import") (part "C-EU-3216"))
    )
    (comp (ref "C106")
      (value "0.1µ")
      (footprint "eagle-import:C3216")
      (libsource (lib "eagle-import") (part "C-EU-3216"))
    )
    (comp (ref "C107")
      (value "500p")
      (footprint "eagle-import:C1608")
      (libsource (lib "eagle-import") (part "C-EU-1608"))
    )
    (comp (ref "C108")
      (value "0.1µ")
      (footprint "eagle-import:C3216")
      (libsource (lib "eagle-import") (part "C-EU-3216"))
    )
    (comp (ref "C109")
      (value "0.01µ")
      (footprint "eagle-import:C3216")
      (libsource (lib "eagle-import") (part "C-EU-3216"))
    )
    (comp (ref "C110")
      (value "0.01µ")
      (footprint "eagle-import:C3216")
      (libsource (lib "eagle-import") (part "C-EU-3216"))
    )
    (comp (ref "C111")
      (value "0.01µ")
      (footprint "eagle-import:C3216")
      (libsource (lib "eagle-import") (part "C-EU-3216"))
    )
    (comp (ref "C112")
      (value "0.01µ")
      (footprint "eagle-import:C3216")
      (libsource (lib "eagle-import") (part "C-EU-3216"))
    )
    (comp (ref "C113")
      (value "0.1µ")
      (footprint "eagle-import:C3216")
      (libsource (lib "eagle-import") (part "C-EU-3216"))
    )
    (comp (ref "C114")
      (value "1µ")
      (footprint "eagle-import:CT3216")
      (libsource (lib "eagle-import") (part "CPOL-3216-A"))
    )
    (comp (ref "C115")
      (value "1µ")
      (footprint "eagle-import:CT3216")
      (libsource (lib "eagle-import") (part "CPOL-3216-A"))
    )
    (comp (ref "C116")
      (value "500p")
      (footprint "eagle-import:C1608")
      (libsource (lib "eagle-import") (part "C-EU-1608"))
    )
    (comp (ref "C117")
      (value "500p")
      (footprint "eagle-import:C1608")
      (libsource (lib "eagle-import") (part "C-EU-1608"))
    )
    (comp (ref "C118")
      (value "0.1µ")
      (footprint "eagle-import:C3216")
      (libsource (lib "eagle-import") (part "C-EU-3216"))
    )
    (comp (ref "C119")
      (value "0.1µ")
      (footprint "eagle-import:C3216")
      (libsource (lib "eagle-import") (part "C-EU-3216"))
    )
    (comp (ref "C120")
      (value "1µ")
      (footprint "eagle-import:CT3216")
      (libsource (lib "eagle-import") (part "CPOL-3216-A"))
    )
    (comp (ref "C121")
      (value "0.1µ")
      (footprint "eagle-import:C3216")
      (libsource (lib "eagle-import") (part "C-EU-3216"))
    )
    (comp (ref "Q1")
      (value "IXTK102N65X2-V")
      (footprint "eagle-import:TO-264P-V")
      (libsource (lib "eagle-import") (part "IXTK102N65X2-V"))
    )
    (comp (ref "Q2")
      (value "IXTK102N65X2-V")
      (footprint "eagle-import:TO-264P-V")
      (libsource (lib "eagle-import") (part "IXTK102N65X2-V"))
    )
    (comp (ref "Q101")
      (value "SIRC10DP")
      (footprint "eagle-import:POWERPAK-SO-8")
      (libsource (lib "eagle-import") (part "SIRC10DP"))
    )
    (comp (ref "Q102")
      (value "SIRC10DP")
      (footprint "eagle-import:POWERPAK-SO-8")
      (libsource (lib "eagle-import") (part "SIRC10DP"))
    )
    (comp (ref "Q103")
      (value "BC817-16SMD")
      (footprint "eagle-import:SOT23-BEC")
      (libsource (lib "eagle-import") (part "BC817SMD-16"))
    )
    (comp (ref "Q104")
      (value "SIRC10DP")
      (footprint "eagle-import:POWERPAK-SO-8")
      (libsource (lib "eagle-import") (part "SIRC10DP"))
    )
    (comp (ref "Q105")
      (value "BC817-16SMD")
      (footprint "eagle-import:SOT23-BEC")
      (libsource (lib "eagle-import") (part "BC817SMD-16"))
    )
    (comp (ref "Q106")
      (value "BC807-16SMD")
      (footprint "eagle-import:SOT23-BEC")
      (libsource (lib "eagle-import") (part "BC807SMD-16"))
    )
    (comp (ref "Q108")
      (value "SIRC10DP")
      (footprint "eagle-import:POWERPAK-SO-8")
      (libsource (lib "eagle-import") (part "SIRC10DP"))
    )
    (comp (ref "Q109")
      (value "SIRC10DP")
      (footprint "eagle-import:POWERPAK-SO-8")
      (libsource (lib "eagle-import") (part "SIRC10DP"))
    )
    (comp (ref "Q110")
      (value "SIRC10DP")
      (footprint "eagle-import:POWERPAK-SO-8")
      (libsource (lib "eagle-import") (part "SIRC10DP"))
    )
    (comp (ref "R101")
      (value "2R")
      (footprint "eagle-import:R2012W")
      (libsource (lib "eagle-import") (part "R-EU-2012"))
    )
    (comp (ref "R102")
      (value "10k")
      (footprint "eagle-import:R1608")
      (libsource (lib "eagle-import") (part "R-EU-1608"))
    )
    (comp (ref "R103")
      (value "1k")
      (footprint "eagle-import:R1608")
      (libsource (lib "eagle-import") (part "R-EU-1608"))
    )
    (comp (ref "R104")
      (value "2R")
      (footprint "eagle-import:R2012W")
      (libsource (lib "eagle-import") (part "R-EU-2012"))
    )
    (comp (ref "R105")
      (value "100k")
      (footprint "eagle-import:R1608")
      (libsource (lib "eagle-import") (part "R-EU-1608"))
    )
    (comp (ref "R106")
      (value "1k")
      (footprint "eagle-import:R1608")
      (libsource (lib "eagle-import") (part "R-EU-1608"))
    )
    (comp (ref "R107")
      (value "2R")
      (footprint "eagle-import:R2012W")
      (libsource (lib "eagle-import") (part "R-EU-2012"))
    )
    (comp (ref "R108")
      (value "2R")
      (footprint "eagle-import:R2012W")
      (libsource (lib "eagle-import") (part "R-EU-2012"))
    )
    (comp (ref "R109")
      (value "0R004")
      (footprint "eagle-import:R6332W")
      (libsource (lib "eagle-import") (part "R-EU-6332"))
    )
    (comp (ref "R110")
      (value "2R")
      (footprint "eagle-import:R3216W")
      (libsource (lib "eagle-import") (part "R-EU-3216"))
    )
    (comp (ref "R111")
      (value "0R004")
      (footprint "eagle-import:R6332W")
      (libsource (lib "eagle-import") (part "R-EU-6332"))
    )
    (comp (ref "R112")
      (value "2R")
      (footprint "eagle-import:R2012W")
      (libsource (lib "eagle-import") (part "R-EU-2012"))
    )
    (comp (ref "R113")
      (value "10k")
      (footprint "eagle-import:R1608")
      (libsource (lib "eagle-import") (part "R-EU-1608"))
    )
    (comp (ref "R114")
      (value "10k")
      (footprint "eagle-import:R1608")
      (libsource (lib "eagle-import") (part "R-EU-1608"))
    )
    (comp (ref "R115")
      (value "2R")
      (footprint "eagle-import:R2012W")
      (libsource (lib "eagle-import") (part "R-EU-2012"))
    )
    (comp (ref "R116")
      (value "10k")
      (footprint "eagle-import:R1608")
      (libsource (lib "eagle-import") (part "R-EU-1608"))
    )
    (comp (ref "R117")
      (value "10k")
      (footprint "eagle-import:R1608")
      (libsource (lib "eagle-import") (part "R-EU-1608"))
    )
    (comp (ref "R118")
      (value "10k")
      (footprint "eagle-import:R1608")
      (libsource (lib "eagle-import") (part "R-EU-1608"))
    )
    (comp (ref "R119")
      (value "10k")
      (footprint "eagle-import:R1608")
      (libsource (lib "eagle-import") (part "R-EU-1608"))
    )
    (comp (ref "R120")
      (value "100R")
      (footprint "eagle-import:R2012W")
      (libsource (lib "eagle-import") (part "R-EU-2012"))
    )
    (comp (ref "R121")
      (value "100R")
      (footprint "eagle-import:R2012W")
      (libsource (lib "eagle-import") (part "R-EU-2012"))
    )
    (comp (ref "R122")
      (value "2R")
      (footprint "eagle-import:R2012W")
      (libsource (lib "eagle-import") (part "R-EU-2012"))
    )
    (comp (ref "R123")
      (value "2R")
      (footprint "eagle-import:R2012W")
      (libsource (lib "eagle-import") (part "R-EU-2012"))
    )
    (comp (ref "R124")
      (value "10k")
      (footprint "eagle-import:R1608")
      (libsource (lib "eagle-import") (part "R-EU-1608"))
    )
    (comp (ref "R125")
      (value "10k")
      (footprint "eagle-import:R1608")
      (libsource (lib "eagle-import") (part "R-EU-1608"))
    )
    (comp (ref "R126")
      (value "10k")
      (footprint "eagle-import:R1608")
      (libsource (lib "eagle-import") (part "R-EU-1608"))
    )
    (comp (ref "R127")
      (value "10k")
      (footprint "eagle-import:R1608")
      (libsource (lib "eagle-import") (part "R-EU-1608"))
    )
    (comp (ref "R128")
      (value "0R004")
      (footprint "eagle-import:R6332W")
      (libsource (lib "eagle-import") (part "R-EU-6332"))
    )
    (comp (ref "R129")
      (value "2R")
      (footprint "eagle-import:R3216W")
      (libsource (lib "eagle-import") (part "R-EU-3216"))
    )
    (comp (ref "R130")
      (value "10k")
      (footprint "eagle-import:R1608")
      (libsource (lib "eagle-import") (part "R-EU-1608"))
    )
    (comp (ref "R131")
      (value "10k")
      (footprint "eagle-import:R1608")
      (libsource (lib "eagle-import") (part "R-EU-1608"))
    )
    (comp (ref "R132")
      (value "0R004")
      (footprint "eagle-import:R6332W")
      (libsource (lib "eagle-import") (part "R-EU-6332"))
    )
    (comp (ref "U101")
      (value "AD420")
      (footprint "eagle-import:SO24W")
      (libsource (lib "eagle-import") (part "AD420RW-24"))
    )
    (comp (ref "U102")
      (value "AD420")
      (footprint "eagle-import:SO24W")
      (libsource (lib "eagle-import") (part "AD420RW-24"))
    )
    (comp (ref "U103")
      (value "LM50")
      (footprint "eagle-import:SOT23W")
      (libsource (lib "eagle-import") (part "LM50"))
    )
    (comp (ref "U104")
      (value "LM50")
      (footprint "eagle-import:SOT23W")
      (libsource (lib "eagle-import") (part "LM50"))
    )
    (comp (ref "U105")
      (value "LT1014I")
      (footprint "eagle-import:SO16W")
      (libsource (lib "eagle-import") (part "LT1014ISW"))
    )
    (comp (ref "U106")
      (value "LTC1865L")
      (footprint "eagle-import:SO8")
      (libsource (lib "eagle-import") (part "LTC1865L"))
    )
  )
  (nets
    (net (code "1") (name "+3V3") (class "Default")
      (node (ref "C120") (pin "+") (pinfunction "+_+") (pintype "passive"))
      (node (ref "C121") (pin "1") (pinfunction "1_1") (pintype "passive"))
      (node (ref "C213") (pin "+") (pinfunction "+_+") (pintype "passive"))
      (node (ref "C214") (pin "+") (pinfunction "+_+") (pintype "passive"))
      (node (ref "C216") (pin "1") (pinfunction "1_1") (pintype "passive"))
      (node (ref "C217") (pin "1") (pinfunction "1_1") (pintype "passive"))
      (node (ref "C220") (pin "+") (pinfunction "+_+") (pintype "passive"))
      (node (ref "C221") (pin "1") (pinfunction "1_1") (pintype "passive"))
      (node (ref "C311") (pin "1") (pinfunction "1_1") (pintype "passive"))
      (node (ref "U106") (pin "8") (pinfunction "VCC_8") (pintype "power_in"))
      (node (ref "U206") (pin "8") (pinfunction "VCC_8") (pintype "power_in"))
      (node (ref "U207") (pin "8") (pinfunction "VCC_8") (pintype "power_in"))
      (node (ref "U208") (pin "8") (pinfunction "VCC_8") (pintype "power_in"))
      (node (ref "U301") (pin "5") (pinfunction "VOUT_5") (pintype "power_in"))
    )
    (net (code "2") (name "+5V") (class "Default")
      (node (ref "C101") (pin "+") (pinfunction "+_+") (pintype "passive"))
      (node (ref "C103") (pin "+") (pinfunction "+_+") (pintype "passive"))
      (node (ref "C105") (pin "1") (pinfunction "1_1") (pintype "passive"))
      (node (ref "C106") (pin "1") (pinfunction "1_1") (pintype "passive"))
      (node (ref "C113") (pin "1") (pinfunction "1_1") (pintype "passive"))
      (node (ref "C303") (pin "1") (pinfunction "1_1") (pintype "passive"))
      (node (ref "C304") (pin "1") (pinfunction "1_1") (pintype "passive"))
      (node (ref "C305") (pin "2") (pinfunction "2_2") (pintype "passive"))
      (node (ref "C312") (pin "+") (pinfunction "+_+") (pintype "passive"))
      (node (ref "C401") (pin "1") (pinfunction "1_1") (pintype "passive"))
      (node (ref "C402") (pin "1") (pinfunction "1_1") (pintype "passive"))
      (node (ref "C403") (pin "1") (pinfunction "1_1") (pintype "passive"))
      (node (ref "C404") (pin "1") (pinfunction "1_1") (pintype "passive"))
      (node (ref "C406") (pin "1") (pinfunction "1_1") (pintype "passive"))
      (node (ref "C407") (pin "1") (pinfunction "1_1") (pintype "passive"))
      (node (ref "C413") (pin "1") (pinfunction "1_1") (pintype "passive"))
      (node (ref "C414") (pin "1") (pinfunction "1_1") (pintype "passive"))
      (node (ref "C417") (pin "1") (pinfunction "1_1") (pintype "passive"))
      (node (ref "C418") (pin "1") (pinfunction "1_1") (pintype "passive"))
      (node (ref "C419") (pin "1") (pinfunction "1_1") (pintype "passive"))
      (node (ref "C420") (pin "1") (pinfunction "1_1") (pintype "passive"))
      (node (ref "IC301") (pin "3") (pinfunction "VO_3") (pintype "passive"))
      (node (ref "L302") (pin "1") (pinfunction "1_1") (pintype "passive"))
      (node (ref "R102") (pin "1") (pinfunction "1_1") (pintype "passive"))
      (node (ref "R401") (pin "2") (pinfunction "2_2") (pintype "passive"))
      (node (ref "R402") (pin "2") (pinfunction "2_2") (pintype "passive"))
      (node (ref "R403") (pin "2") (pinfunction "2_2") (pintype "passive"))
      (node (ref "R404") (pin "2") (pinfunction "2_2") (pintype "passive"))
      (node (ref "R405") (pin "2") (pinfunction "2_2") (pintype "passive"))
      (node (ref "R406") (pin "2") (pinfunction "2_2") (pintype "passive"))
      (node (ref "R407") (pin "2") (pinfunction "2_2") (pintype "passive"))
      (node (ref "R408") (pin "2") (pinfunction "2_2") (pintype "passive"))
      (node (ref "R409") (pin "2") (pinfunction "2_2") (pintype "passive"))
      (node (ref "R410") (pin "2") (pinfunction "2_2") (pintype "passive"))
      (node (ref "R411") (pin "2") (pinfunction "2_2") (pintype "passive"))
      (node (ref "R412") (pin "2") (pinfunction "2_2") (pintype "passive"))
      (node (ref "R413") (pin "2") (pinfunction "2_2") (pintype "passive"))
      (node (ref "R414") (pin "2") (pinfunction "2_2") (pintype "passive"))
      (node (ref "R415") (pin "2") (pinfunction "2_2") (pintype "passive"))
      (node (ref "R416") (pin "2") (pinfunction "2_2") (pintype "passive"))
      (node (ref "R417") (pin "2") (pinfunction "2_2") (pintype "passive"))
      (node (ref "R418") (pin "2") (pinfunction "2_2") (pintype "passive"))
      (node (ref "R419") (pin "2") (pinfunction "2_2") (pintype "passive"))
      (node (ref "R420") (pin "2") (pinfunction "2_2") (pintype "passive"))
      (node (ref "R421") (pin "2") (pinfunction "2_2") (pintype "passive"))
      (node (ref "R422") (pin "2") (pinfunction "2_2") (pintype "passive"))
      (node (ref "R423") (pin "2") (pinfunction "2_2") (pintype "passive"))
      (node (ref "R424") (pin "2") (pinfunction "2_2") (pintype "passive"))
      (node (ref "U101") (pin "2") (pinfunction "VLL_2") (pintype "bidirectional"))
      (node (ref "U102") (pin "2") (pinfunction "VLL_2") (pintype "bidirectional"))
      (node (ref "U103") (pin "1") (pinfunction "+V_1") (pintype "power_in"))
      (node (ref "U104") (pin "1") (pinfunction "+V_1") (pintype "power_in"))
      (node (ref "U301") (pin "1") (pinfunction "VIN_1") (pintype "power_in"))
      (node (ref "U301") (pin "3") (pinfunction "ON/OFF_3") (pintype "input"))
      (node (ref "U302") (pin "12") (pinfunction "V+_12") (pintype "input"))
      (node (ref "U302") (pin "13") (pinfunction "V+_13") (pintype "input"))
      (node (ref "U302") (pin "3") (pinfunction "AV+_3") (pintype "input"))
      (node (ref "U302") (pin "4") (pinfunction "V+_4") (pintype "input"))
      (node (ref "U302") (pin "5") (pinfunction "V+_5") (pintype "input"))
      (node (ref "U401") (pin "8") (pinfunction "VCC_8") (pintype "power_in"))
      (node (ref "U402") (pin "8") (pinfunction "VCC_8") (pintype "power_in"))
      (node (ref "U403") (pin "8") (pinfunction "VCC_8") (pintype "power_in"))
      (node (ref "U404") (pin "8") (pinfunction "VCC_8") (pintype "power_in"))
      (node (ref "U405") (pin "8") (pinfunction "VCC_8") (pintype "power_in"))
      (node (ref "U406") (pin "8") (pinfunction "VCC_8") (pintype "power_in"))
    )
    (net (code "3") (name "+12V") (class "Default")
      (node (ref "C102") (pin "1") (pinfunction "1_1") (pintype "passive"))
      (node (ref "C104") (pin "1") (pinfunction "1_1") (pintype "passive"))
      (node (ref "C108") (pin "1") (pinfunction "1_1") (pintype "passive"))
      (node (ref "C109") (pin "1") (pinfunction "1_1") (pintype "passive"))
      (node (ref "C110") (pin "1") (pinfunction "1_1") (pintype "passive"))
      (node (ref "C111") (pin "1") (pinfunction "1_1") (pintype "passive"))
      (node (ref "C112") (pin "1") (pinfunction "1_1") (pintype "passive"))
      (node (ref "C301") (pin "1") (pinfunction "1_1") (pintype "passive"))
      (node (ref "C302") (pin "+") (pinfunction "+_+") (pintype "passive"))
      (node (ref "IC301") (pin "1") (pinfunction "VI_1") (pintype "input"))
      (node (ref "J301") (pin "3") (pinfunction "3_3") (pintype "passive"))
      (node (ref "Q105") (pin "C") (pinfunction "C_C") (pintype "passive"))
      (node (ref "R105") (pin "2") (pinfunction "2_2") (pintype "passive"))
      (node (ref "R106") (pin "2") (pinfunction "2_2") (pintype "passive"))
      (node (ref "U101") (pin "23") (pinfunction "VCC_23") (pintype "bidirectional"))
      (node (ref "U102") (pin "23") (pinfunction "VCC_23") (pintype "bidirectional"))
    )
    (net (code "4") (name "+15V") (class "Default")
      (node (ref "C118") (pin "1") (pinfunction "1_1") (pintype "passive"))
      (node (ref "C201") (pin "1") (pinfunction "1_1") (pintype "passive"))
      (node (ref "C202") (pin "1") (pinfunction "1_1") (pintype "passive"))
      (node (ref "C203") (pin "1") (pinfunction "1_1") (pintype "passive"))
      (node (ref "C204") (pin "1") (pinfunction "1_1") (pintype "passive"))
      (node (ref "C215") (pin "1") (pinfunction "1_1") (pintype "passive"))
      (node (ref "C313") (pin "+") (pinfunction "+_+") (pintype "passive"))
      (node (ref "D301") (pin "C") (pinfunction "C_C") (pintype "passive"))
      (node (ref "U105") (pin "4") (pinfunction "V+_4") (pintype "power_in"))
      (node (ref "U201") (pin "7") (pinfunction "+V_7") (pintype "power_in"))
      (node (ref "U202") (pin "7") (pinfunction "+V_7") (pintype "power_in"))
      (node (ref "U203") (pin "7") (pinfunction "+V_7") (pintype "power_in"))
      (node (ref "U204") (pin "7") (pinfunction "+V_7") (pintype "power_in"))
      (node (ref "U205") (pin "7") (pinfunction "+V_7") (pintype "power_in"))
      (node (ref "U302") (pin "16") (pinfunction "FB+_16") (pintype "input"))
    )
    (net (code "5") (name "-15V") (class "Default")
      (node (ref "C119") (pin "1") (pinfunction "1_1") (pintype "passive"))
      (node (ref "C205") (pin "1") (pinfunction "1_1") (pintype "passive"))
      (node (ref "C206") (pin "1") (pinfunction "1_1") (pintype "passive"))
      (node (ref "C207") (pin "1") (pinfunction "1_1") (pintype "passive"))
      (node (ref "C208") (pin "1") (pinfunction "1_1") (pintype "passive"))
      (node (ref "C219") (pin "1") (pinfunction "1_1") (pintype "passive"))
      (node (ref "C314") (pin "-") (pinfunction "-_-") (pintype "passive"))
      (node (ref "D302") (pin "A") (pinfunction "A_A") (pintype "passive"))
      (node (ref "U105") (pin "13") (pinfunction "V-_13") (pintype "power_in"))
      (node (ref "U201") (pin "4") (pinfunction "-V_4") (pintype "power_in"))
      (node (ref "U202") (pin "4") (pinfunction "-V_4") (pintype "power_in"))
      (node (ref "U203") (pin "4") (pinfunction "-V_4") (pintype "power_in"))
      (node (ref "U204") (pin "4") (pinfunction "-V_4") (pintype "power_in"))
      (node (ref "U205") (pin "4") (pinfunction "-V_4") (pintype "power_in"))
      (node (ref "U302") (pin "9") (pinfunction "FB-_9") (pintype "input"))
    )
    (net (code "6") (name "BYP") (class "Default")
      (node (ref "Q403") (pin "B") (pinfunction "B_B") (pintype "passive"))
    )
    (net (code "7") (name "BYP_G") (class "Default")
      (node (ref "Q105") (pin "E") (pinfunction "E_E") (pintype "passive"))
      (node (ref "Q106") (pin "E") (pinfunction "E_E") (pintype "passive"))
      (node (ref "R101") (pin "1") (pinfunction "1_1") (pintype "passive"))
      (node (ref "R104") (pin "1") (pinfunction "1_1") (pintype "passive"))
      (node (ref "R108") (pin "1") (pinfunction "1_1") (pintype "passive"))
      (node (ref "R112") (pin "1") (pinfunction "1_1") (pintype "passive"))
      (node (ref "R115") (pin "1") (pinfunction "1_1") (pintype "passive"))
      (node (ref "R123") (pin "1") (pinfunction "1_1") (pintype "passive"))
    )
    (net (code "8") (name "BYP_I") (class "Default")
      (node (ref "C107") (pin "1") (pinfunction "1_1") (pintype "passive"))
      (node (ref "C410") (pin "1") (pinfunction "1_1") (pintype "passive"))
      (node (ref "R103") (pin "1") (pinfunction "1_1") (pintype "passive"))
      (node (ref "R410") (pin "1") (pinfunction "1_1") (pintype "passive"))
      (node (ref "U403") (pin "7") (pinfunction "VO1_7") (pintype "output"))
    )
    (net (code "9") (name "CLR_DAC") (class "Default")
      (node (ref "Q401") (pin "B") (pinfunction "B_B") (pintype "passive"))
    )
    (net (code "10") (name "CLR_DAC_I") (class "Default")
      (node (ref "C405") (pin "1") (pinfunction "1_1") (pintype "passive"))
      (node (ref "R407") (pin "1") (pinfunction "1_1") (pintype "passive"))
      (node (ref "U101") (pin "6") (pinfunction "CLR_6") (pintype "bidirectional"))
      (node (ref "U102") (pin "6") (pinfunction "CLR_6") (pintype "bidirectional"))
      (node (ref "U401") (pin "7") (pinfunction "VO1_7") (pintype "output"))
    )
    (net (code "11") (name "CSENSE1_H") (class "Default")
      (node (ref "Q101") (pin "1") (pinfunction "S_1") (pintype "passive"))
      (node (ref "Q101") (pin "2") (pinfunction "S_2") (pintype "passive"))
      (node (ref "Q101") (pin "3") (pinfunction "S_3") (pintype "passive"))
      (node (ref "Q102") (pin "1") (pinfunction "S_1") (pintype "passive"))
      (node (ref "Q102") (pin "2") (pinfunction "S_2") (pintype "passive"))
      (node (ref "Q102") (pin "3") (pinfunction "S_3") (pintype "passive"))
      (node (ref "Q104") (pin "1") (pinfunction "S_1") (pintype "passive"))
      (node (ref "Q104") (pin "2") (pinfunction "S_2") (pintype "passive"))
      (node (ref "Q104") (pin "3") (pinfunction "S_3") (pintype "passive"))
      (node (ref "R109") (pin "2") (pinfunction "2_2") (pintype "passive"))
      (node (ref "R110") (pin "1") (pinfunction "1_1") (pintype "passive"))
      (node (ref "R111") (pin "2") (pinfunction "2_2") (pintype "passive"))
      (node (ref "U201") (pin "3") (pinfunction "+_3") (pintype "input"))
      (node (ref "U202") (pin "2") (pinfunction "-_2") (pintype "input"))
    )
    (net (code "12") (name "CSENSE1_L") (class "Default")
      (node (ref "PAD603") (pin "1") (pinfunction "P_1") (pintype "passive"))
      (node (ref "PAD604") (pin "1") (pinfunction "P_1") (pintype "passive"))
      (node (ref "Q1") (pin "3") (pinfunction "S_3") (pintype "passive"))
      (node (ref "Q101") (pin "5") (pinfunction "D_5") (pintype "passive"))
      (node (ref "Q102") (pin "5") (pinfunction "D_5") (pintype "passive"))
      (node (ref "Q104") (pin "5") (pinfunction "D_5") (pintype "passive"))
      (node (ref "R110") (pin "2") (pinfunction "2_2") (pintype "passive"))
      (node (ref "R113") (pin "1") (pinfunction "1_1") (pintype "passive"))
      (node (ref "U202") (pin "3") (pinfunction "+_3") (pintype "input"))
    )
    (net (code "13") (name "CSENSE2_H") (class "Default")
      (node (ref "Q108") (pin "1") (pinfunction "S_1") (pintype "passive"))
      (node (ref "Q108") (pin "2") (pinfunction "S_2") (pintype "passive"))
      (node (ref "Q108") (pin "3") (pinfunction "S_3") (pintype "passive"))
      (node (ref "Q109") (pin "1") (pinfunction "S_1") (pintype "passive"))
      (node (ref "Q109") (pin "2") (pinfunction "S_2") (pintype "passive"))
      (node (ref "Q109") (pin "3") (pinfunction "S_3") (pintype "passive"))
      (node (ref "Q110") (pin "1") (pinfunction "S_1") (pintype "passive"))
      (node (ref "Q110") (pin "2") (pinfunction "S_2") (pintype "passive"))
      (node (ref "Q110") (pin "3") (pinfunction "S_3") (pintype "passive"))
      (node (ref "R128") (pin "2") (pinfunction "2_2") (pintype "passive"))
      (node (ref "R129") (pin "1") (pinfunction "1_1") (pintype "passive"))
      (node (ref "R132") (pin "2") (pinfunction "2_2") (pintype "passive"))
      (node (ref "U203") (pin "2") (pinfunction "-_2") (pintype "input"))
      (node (ref "U204") (pin "3") (pinfunction "+_3") (pintype "input"))
    )
    (net (code "14") (name "CSENSE2_L") (class "Default")
      (node (ref "PAD605") (pin "1") (pinfunction "P_1") (pintype "passive"))
      (node (ref "PAD606") (pin "1") (pinfunction "P_1") (pintype "passive"))
      (node (ref "Q108") (pin "5") (pinfunction "D_5") (pintype "passive"))
      (node (ref "Q109") (pin "5") (pinfunction "D_5") (pintype "passive"))
      (node (ref "Q110") (pin "5") (pinfunction "D_5") (pintype "passive"))
      (node (ref "Q2") (pin "3") (pinfunction "S_3") (pintype "passive"))
      (node (ref "R114") (pin "1") (pinfunction "1_1") (pintype "passive"))
      (node (ref "R129") (pin "2") (pinfunction "2_2") (pintype "passive"))
      (node (ref "U203") (pin "3") (pinfunction "+_3") (pintype "input"))
    )
    (net (code "15") (name "DAC1_VOUT") (class "Default")
      (node (ref "U101") (pin "17") (pinfunction "VOUT_17") (pintype "bidirectional"))
      (node (ref "U105") (pin "14") (pinfunction "+IN_14") (pintype "input"))
    )
    (net (code "16") (name "DAC2_VOUT") (class "Default")
      (node (ref "U102") (pin "17") (pinfunction "VOUT_17") (pintype "bidirectional"))
      (node (ref "U105") (pin "12") (pinfunction "+IN_12") (pintype "input"))
    )
    (net (code "17") (name "DAC_FAULT") (class "Default")
      (node (ref "C411") (pin "1") (pinfunction "1_1") (pintype "passive"))
      (node (ref "R411") (pin "1") (pinfunction "1_1") (pintype "passive"))
      (node (ref "U402") (pin "6") (pinfunction "VO2_6") (pintype "output"))
    )
    (net (code "18") (name "FLT_DAC_I") (class "Default")
      (node (ref "Q405") (pin "B") (pinfunction "B_B") (pintype "passive"))
      (node (ref "R102") (pin "2") (pinfunction "2_2") (pintype "passive"))
      (node (ref "U101") (pin "3") (pinfunction "FLT_3") (pintype "bidirectional"))
      (node (ref "U102") (pin "3") (pinfunction "FLT_3") (pintype "bidirectional"))
    )
    (net (code "19") (name "GATE1") (class "Default")
      (node (ref "PAD607") (pin "1") (pinfunction "P_1") (pintype "passive"))
      (node (ref "PAD608") (pin "1") (pinfunction "P_1") (pintype "passive"))
      (node (ref "Q1") (pin "1") (pinfunction "G_1") (pintype "passive"))
      (node (ref "R107") (pin "2") (pinfunction "2_2") (pintype "passive"))
    )
    (net (code "20") (name "GATE2") (class "Default")
      (node (ref "PAD609") (pin "1") (pinfunction "P_1") (pintype "passive"))
      (node (ref "PAD610") (pin "1") (pinfunction "P_1") (pintype "passive"))
      (node (ref "Q2") (pin "1") (pinfunction "G_1") (pintype "passive"))
      (node (ref "R122") (pin "2") (pinfunction "2_2") (pintype "passive"))
    )
    (net (code "21") (name "GND") (class "Default")
      (node (ref "C101") (pin "-") (pinfunction "-_-") (pintype "passive"))
      (node (ref "C102") (pin "2") (pinfunction "2_2") (pintype "passive"))
      (node (ref "C103") (pin "-") (pinfunction "-_-") (pintype "passive"))
      (node (ref "C104") (pin "2") (pinfunction "2_2") (pintype "passive"))
      (node (ref "C105") (pin "2") (pinfunction "2_2") (pintype "passive"))
      (node (ref "C106") (pin "2") (pinfunction "2_2") (pintype "passive"))
      (node (ref "C108") (pin "2") (pinfunction "2_2") (pintype "passive"))
      (node (ref "C113") (pin "2") (pinfunction "2_2") (pintype "passive"))
      (node (ref "C114") (pin "-") (pinfunction "-_-") (pintype "passive"))
      (node (ref "C115") (pin "-") (pinfunction "-_-") (pintype "passive"))
      (node (ref "C116") (pin "2") (pinfunction "2_2") (pintype "passive"))
      (node (ref "C117") (pin "2") (pinfunction "2_2") (pintype "passive"))
      (node (ref "C118") (pin "2") (pinfunction "2_2") (pintype "passive"))
      (node (ref "C119") (pin "2") (pinfunction "2_2") (pintype "passive"))
      (node (ref "C120") (pin "-") (pinfunction "-_-") (pintype "passive"))
      (node (ref "C121") (pin "2") (pinfunction "2_2") (pintype "passive"))
      (node (ref "C201") (pin "2") (pinfunction "2_2") (pintype "passive"))
      (node (ref "C202") (pin "2") (pinfunction "2_2") (pintype "passive"))
      (node (ref "C203") (pin "2") (pinfunction "2_2") (pintype "passive"))
      (node (ref "C204") (pin "2") (pinfunction "2_2") (pintype "passive"))
      (node (ref "C205") (pin "2") (pinfunction "2_2") (pintype "passive"))
      (node (ref "C206") (pin "2") (pinfunction "2_2") (pintype "passive"))
      (node (ref "C207") (pin "2") (pinfunction "2_2") (pintype "passive"))
      (node (ref "C208") (pin "2") (pinfunction "2_2") (pintype "passive"))
      (node (ref "C209") (pin "2") (pinfunction "2_2") (pintype "passive"))
      (node (ref "C210") (pin "2") (pinfunction "2_2") (pintype "passive"))
      (node (ref "C211") (pin "2") (pinfunction "2_2") (pintype "passive"))
      (node (ref "C212") (pin "2") (pinfunction "2_2") (pintype "passive"))
      (node (ref "C213") (pin "-") (pinfunction "-_-") (pintype "passive"))
      (node (ref "C214") (pin "-") (pinfunction "-_-") (pintype "passive"))
      (node (ref "C215") (pin "2") (pinfunction "2_2") (pintype "passive"))
      (node (ref "C216") (pin "2") (pinfunction "2_2") (pintype "passive"))
      (node (ref "C217") (pin "2") (pinfunction "2_2") (pintype "passive"))
      (node (ref "C218") (pin "2") (pinfunction "2_2") (pintype "passive"))
      (node (ref "C219") (pin "2") (pinfunction "2_2") (pintype "passive"))
      (node (ref "C220") (pin "-") (pinfunction "-_-") (pintype "passive"))
      (node (ref "C221") (pin "2") (pinfunction "2_2") (pintype "passive"))
      (node (ref "C301") (pin "2") (pinfunction "2_2") (pintype "passive"))
      (node (ref "C302") (pin "-") (pinfunction "-_-") (pintype "passive"))
      (node (ref "C303") (pin "2") (pinfunction "2_2") (pintype "passive"))
      (node (ref "C304") (pin "2") (pinfunction "2_2") (pintype "passive"))
      (node (ref "C305") (pin "1") (pinfunction "1_1") (pintype "passive"))
      (node (ref "C306") (pin "-") (pinfunction "-_-") (pintype "passive"))
      (node (ref "C307") (pin "1") (pinfunction "1_1") (pintype "passive"))
      (node (ref "C308") (pin "-") (pinfunction "-_-") (pintype "passive"))
      (node (ref "C309") (pin "2") (pinfunction "2_2") (pintype "passive"))
      (node (ref "C310") (pin "2") (pinfunction "2_2") (pintype "passive"))
      (node (ref "C311") (pin "2") (pinfunction "2_2") (pintype "passive"))
      (node (ref "C312") (pin "-") (pinfunction "-_-") (pintype "passive"))
      (node (ref "C313") (pin "-") (pinfunction "-_-") (pintype "passive"))
      (node (ref "C314") (pin "+") (pinfunction "+_+") (pintype "passive"))
      (node (ref "C401") (pin "2") (pinfunction "2_2") (pintype "passive"))
      (node (ref "C402") (pin "2") (pinfunction "2_2") (pintype "passive"))
      (node (ref "C403") (pin "2") (pinfunction "2_2") (pintype "passive"))
      (node (ref "C404") (pin "2") (pinfunction "2_2") (pintype "passive"))
      (node (ref "C405") (pin "2") (pinfunction "2_2") (pintype "passive"))
      (node (ref "C406") (pin "2") (pinfunction "2_2") (pintype "passive"))
      (node (ref "C407") (pin "2") (pinfunction "2_2") (pintype "passive"))
      (node (ref "C408") (pin "2") (pinfunction "2_2") (pintype "passive"))
      (node (ref "C409") (pin "2") (pinfunction "2_2") (pintype "passive"))
      (node (ref "C410") (pin "2") (pinfunction "2_2") (pintype "passive"))
      (node (ref "C411") (pin "2") (pinfunction "2_2") (pintype "passive"))
      (node (ref "C412") (pin "2") (pinfunction "2_2") (pintype "passive"))
      (node (ref "C413") (pin "2") (pinfunction "2_2") (pintype "passive"))
      (node (ref "C414") (pin "2") (pinfunction "2_2") (pintype "passive"))
      (node (ref "C415") (pin "2") (pinfunction "2_2") (pintype "passive"))
      (node (ref "C416") (pin "2") (pinfunction "2_2") (pintype "passive"))
      (node (ref "C417") (pin "2") (pinfunction "2_2") (pintype "passive"))
      (node (ref "C418") (pin "2") (pinfunction "2_2") (pintype "passive"))
      (node (ref "C419") (pin "2") (pinfunction "2_2") (pintype "passive"))
      (node (ref "C420") (pin "2") (pinfunction "2_2") (pintype "passive"))
      (node (ref "C421") (pin "2") (pinfunction "2_2") (pintype "passive"))
      (node (ref "C422") (pin "2") (pinfunction "2_2") (pintype "passive"))
      (node (ref "C423") (pin "2") (pinfunction "2_2") (pintype "passive"))
      (node (ref "C424") (pin "2") (pinfunction "2_2") (pintype "passive"))
      (node (ref "IC301") (pin "2") (pinfunction "GND_2") (pintype "passive"))
      (node (ref "J301") (pin "1") (pinfunction "1_1") (pintype "passive"))
      (node (ref "J301") (pin "2") (pinfunction "2_2") (pintype "passive"))
      (node (ref "L301") (pin "2") (pinfunction "2_2") (pintype "passive"))
      (node (ref "Q103") (pin "E") (pinfunction "E_E") (pintype "passive"))
      (node (ref "Q106") (pin "C") (pinfunction "C_C") (pintype "passive"))
      (node (ref "Q401") (pin "C") (pinfunction "C_C") (pintype "passive"))
      (node (ref "Q402") (pin "C") (pinfunction "C_C") (pintype "passive"))
      (node (ref "Q403") (pin "C") (pinfunction "C_C") (pintype "passive"))
      (node (ref "Q404") (pin "C") (pinfunction "C_C") (pintype "passive"))
      (node (ref "Q405") (pin "C") (pinfunction "C_C") (pintype "passive"))
      (node (ref "Q406") (pin "C") (pinfunction "C_C") (pintype "passive"))
      (node (ref "Q407") (pin "C") (pinfunction "C_C") (pintype "passive"))
      (node (ref "Q408") (pin "C") (pinfunction "C_C") (pintype "passive"))
      (node (ref "Q409") (pin "C") (pinfunction "C_C") (pintype "passive"))
      (node (ref "Q410") (pin "C") (pinfunction "C_C") (pintype "passive"))
      (node (ref "Q411") (pin "C") (pinfunction "C_C") (pintype "passive"))
      (node (ref "Q412") (pin "C") (pinfunction "C_C") (pintype "passive"))
      (node (ref "R130") (pin "1") (pinfunction "1_1") (pintype "passive"))
      (node (ref "R131") (pin "1") (pinfunction "1_1") (pintype "passive"))
      (node (ref "R214") (pin "1") (pinfunction "1_1") (pintype "passive"))
      (node (ref "R217") (pin "1") (pinfunction "1_1") (pintype "passive"))
      (node (ref "U101") (pin "11") (pinfunction "GND_11") (pintype "bidirectional"))
      (node (ref "U101") (pin "4") (pinfunction "RS2_4") (pintype "bidirectional"))
      (node (ref "U101") (pin "5") (pinfunction "RS1_5") (pintype "bidirectional"))
      (node (ref "U102") (pin "11") (pinfunction "GND_11") (pintype "bidirectional"))
      (node (ref "U102") (pin "4") (pinfunction "RS2_4") (pintype "bidirectional"))
      (node (ref "U102") (pin "5") (pinfunction "RS1_5") (pintype "bidirectional"))
      (node (ref "U103") (pin "3") (pinfunction "GND_3") (pintype "power_in"))
      (node (ref "U104") (pin "3") (pinfunction "GND_3") (pintype "power_in"))
      (node (ref "U106") (pin "4") (pinfunction "GND_4") (pintype "bidirectional"))
      (node (ref "U201") (pin "5") (pinfunction "REF_5") (pintype "passive"))
      (node (ref "U202") (pin "5") (pinfunction "REF_5") (pintype "passive"))
      (node (ref "U203") (pin "5") (pinfunction "REF_5") (pintype "passive"))
      (node (ref "U204") (pin "5") (pinfunction "REF_5") (pintype "passive"))
      (node (ref "U205") (pin "5") (pinfunction "REF_5") (pintype "passive"))
      (node (ref "U206") (pin "4") (pinfunction "GND_4") (pintype "bidirectional"))
      (node (ref "U207") (pin "4") (pinfunction "GND_4") (pintype "bidirectional"))
      (node (ref "U208") (pin "4") (pinfunction "GND_4") (pintype "bidirectional"))
      (node (ref "U301") (pin "2") (pinfunction "GND_2") (pintype "power_in"))
      (node (ref "U302") (pin "11") (pinfunction "12/15_11") (pintype "input"))
      (node (ref "U302") (pin "14") (pinfunction "GND_14") (pintype "power_in"))
      (node (ref "U302") (pin "2") (pinfunction "AGND_2") (pintype "power_in"))
      (node (ref "U401") (pin "2") (pinfunction "C1_2") (pintype "input"))
      (node (ref "U401") (pin "3") (pinfunction "C2_3") (pintype "input"))
      (node (ref "U401") (pin "5") (pinfunction "GND_5") (pintype "power_in"))
      (node (ref "U402") (pin "2") (pinfunction "C1_2") (pintype "input"))
      (node (ref "U402") (pin "3") (pinfunction "C2_3") (pintype "input"))
      (node (ref "U402") (pin "5") (pinfunction "GND_5") (pintype "power_in"))
      (node (ref "U403") (pin "2") (pinfunction "C1_2") (pintype "input"))
      (node (ref "U403") (pin "3") (pinfunction "C2_3") (pintype "input"))
      (node (ref "U403") (pin "5") (pinfunction "GND_5") (pintype "power_in"))
      (node (ref "U404") (pin "2") (pinfunction "C1_2") (pintype "input"))
      (node (ref "U404") (pin "3") (pinfunction "C2_3") (pintype "input"))
      (node (ref "U404") (pin "5") (pinfunction "GND_5") (pintype "power_in"))
      (node (ref "U405") (pin "2") (pinfunction "C1_2") (pintype "input"))
      (node (ref "U405") (pin "3") (pinfunction "C2_3") (pintype "input"))
      (node (ref "U405") (pin "5") (pinfunction "GND_5") (pintype "power_in"))
      (node (ref "U406") (pin "2") (pinfunction "C1_2") (pintype "input"))
      (node (ref "U406") (pin "3") (pinfunction "C2_3") (pintype "input"))
      (node (ref "U406") (pin "5") (pinfunction "GND_5") (pintype "power_in"))
    )
    (net (code "22") (name "LQ1_G") (class "Default")
      (node (ref "R107") (pin "1") (pinfunction "1_1") (pintype "passive"))
      (node (ref "R126") (pin "2") (pinfunction "2_2") (pintype "passive"))
      (node (ref "R130") (pin "2") (pinfunction "2_2") (pintype "passive"))
      (node (ref "U105") (pin "16") (pinfunction "OUT_16") (pintype "output"))
    )
    (net (code "23") (name "LQ2_G") (class "Default")
      (node (ref "R122") (pin "1") (pinfunction "1_1") (pintype "passive"))
      (node (ref "R127") (pin "2") (pinfunction "2_2") (pintype "passive"))
      (node (ref "R131") (pin "2") (pinfunction "2_2") (pintype "passive"))
      (node (ref "U105") (pin "10") (pinfunction "OUT_10") (pintype "output"))
    )
    (net (code "24") (name "MISO") (class "Default")
      (node (ref "C409") (pin "1") (pinfunction "1_1") (pintype "passive"))
      (node (ref "R409") (pin "1") (pinfunction "1_1") (pintype "passive"))
      (node (ref "U402") (pin "7") (pinfunction "VO1_7") (pintype "output"))
    )
    (net (code "25") (name "MISO_I") (class "Default")
      (node (ref "Q402") (pin "B") (pinfunction "B_B") (pintype "passive"))
      (node (ref "U106") (pin "6") (pinfunction "SDO_6") (pintype "output"))
      (node (ref "U206") (pin "6") (pinfunction "SDO_6") (pintype "output"))
      (node (ref "U207") (pin "6") (pinfunction "SDO_6") (pintype "output"))
      (node (ref "U208") (pin "6") (pinfunction "SDO_6") (pintype "output"))
    )
    (net (code "26") (name "MOSI") (class "Default")
      (node (ref "Q408") (pin "B") (pinfunction "B_B") (pintype "passive"))
    )
    (net (code "27") (name "MOSI_I") (class "Default")
      (node (ref "C416") (pin "1") (pinfunction "1_1") (pintype "passive"))
      (node (ref "R416") (pin "1") (pinfunction "1_1") (pintype "passive"))
      (node (ref "U101") (pin "9") (pinfunction "SDI_9") (pintype "bidirectional"))
      (node (ref "U106") (pin "5") (pinfunction "SDI_5") (pintype "input"))
      (node (ref "U206") (pin "5") (pinfunction "SDI_5") (pintype "input"))
      (node (ref "U207") (pin "5") (pinfunction "SDI_5") (pintype "input"))
      (node (ref "U208") (pin "5") (pinfunction "SDI_5") (pintype "input"))
      (node (ref "U404") (pin "6") (pinfunction "VO2_6") (pintype "output"))
    )
    (net (code "28") (name "Net-(C107-Pad2)") (class "Default")
      (node (ref "C107") (pin "2") (pinfunction "2_2") (pintype "passive"))
      (node (ref "Q103") (pin "B") (pinfunction "B_B") (pintype "passive"))
      (node (ref "R103") (pin "2") (pinfunction "2_2") (pintype "passive"))
      (node (ref "R105") (pin "1") (pinfunction "1_1") (pintype "passive"))
    )
    (net (code "29") (name "Net-(MOV201-Pad2)") (class "Default")
      (node (ref "MOV201") (pin "2") (pinfunction "2_2") (pintype "passive"))
      (node (ref "MOV202") (pin "1") (pinfunction "1_1") (pintype "passive"))
    )
    (net (code "30") (name "Net-(MOV202-Pad2)") (class "Default")
      (node (ref "MOV202") (pin "2") (pinfunction "2_2") (pintype "passive"))
      (node (ref "MOV203") (pin "1") (pinfunction "1_1") (pintype "passive"))
    )
    (net (code "31") (name "Net-(MOV203-Pad2)") (class "Default")
      (node (ref "MOV203") (pin "2") (pinfunction "2_2") (pintype "passive"))
      (node (ref "MOV204") (pin "1") (pinfunction "1_1") (pintype "passive"))
    )
    (net (code "32") (name "Net-(Q101-G)") (class "Default")
      (node (ref "Q101") (pin "4") (pinfunction "G_4") (pintype "passive"))
      (node (ref "R101") (pin "2") (pinfunction "2_2") (pintype "passive"))
    )
    (net (code "33") (name "Net-(Q102-G)") (class "Default")
      (node (ref "Q102") (pin "4") (pinfunction "G_4") (pintype "passive"))
      (node (ref "R104") (pin "2") (pinfunction "2_2") (pintype "passive"))
    )
    (net (code "34") (name "Net-(Q103-PadC)") (class "Default")
      (node (ref "Q103") (pin "C") (pinfunction "C_C") (pintype "passive"))
      (node (ref "Q105") (pin "B") (pinfunction "B_B") (pintype "passive"))
      (node (ref "Q106") (pin "B") (pinfunction "B_B") (pintype "passive"))
      (node (ref "R106") (pin "1") (pinfunction "1_1") (pintype "passive"))
    )
    (net (code "35") (name "Net-(Q104-G)") (class "Default")
      (node (ref "Q104") (pin "4") (pinfunction "G_4") (pintype "passive"))
      (node (ref "R108") (pin "2") (pinfunction "2_2") (pintype "passive"))
    )
    (net (code "36") (name "Net-(Q108-G)") (class "Default")
      (node (ref "Q108") (pin "4") (pinfunction "G_4") (pintype "passive"))
      (node (ref "R112") (pin "2") (pinfunction "2_2") (pintype "passive"))
    )
    (net (code "37") (name "Net-(Q109-G)") (class "Default")
      (node (ref "Q109") (pin "4") (pinfunction "G_4") (pintype "passive"))
      (node (ref "R115") (pin "2") (pinfunction "2_2") (pintype "passive"))
    )
    (net (code "38") (name "Net-(Q110-G)") (class "Default")
      (node (ref "Q110") (pin "4") (pinfunction "G_4") (pintype "passive"))
      (node (ref "R123") (pin "2") (pinfunction "2_2") (pintype "passive"))
    )
    (net (code "39") (name "Net-(R201-Pad1)") (class "Default")
      (node (ref "R201") (pin "1") (pinfunction "1_1") (pintype "passive"))
      (node (ref "U201") (pin "8") (pinfunction "RG_8") (pintype "passive"))
    )
    (net (code "40") (name "Net-(R201-Pad2)") (class "Default")
      (node (ref "R201") (pin "2") (pinfunction "2_2") (pintype "passive"))
      (node (ref "U201") (pin "1") (pinfunction "RG_1") (pintype "passive"))
    )
    (net (code "41") (name "Net-(R202-Pad1)") (class "Default")
      (node (ref "R202") (pin "1") (pinfunction "1_1") (pintype "passive"))
      (node (ref "U202") (pin "8") (pinfunction "RG_8") (pintype "passive"))
    )
    (net (code "42") (name "Net-(R202-Pad2)") (class "Default")
      (node (ref "R202") (pin "2") (pinfunction "2_2") (pintype "passive"))
      (node (ref "U202") (pin "1") (pinfunction "RG_1") (pintype "passive"))
    )
    (net (code "43") (name "Net-(R203-Pad1)") (class "Default")
      (node (ref "R203") (pin "1") (pinfunction "1_1") (pintype "passive"))
      (node (ref "U203") (pin "8") (pinfunction "RG_8") (pintype "passive"))
    )
    (net (code "44") (name "Net-(R203-Pad2)") (class "Default")
      (node (ref "R203") (pin "2") (pinfunction "2_2") (pintype "passive"))
      (node (ref "U203") (pin "1") (pinfunction "RG_1") (pintype "passive"))
    )
    (net (code "45") (name "Net-(R204-Pad1)") (class "Default")
      (node (ref "R204") (pin "1") (pinfunction "1_1") (pintype "passive"))
      (node (ref "U204") (pin "8") (pinfunction "RG_8") (pintype "passive"))
    )
    (net (code "46") (name "Net-(R204-Pad2)") (class "Default")
      (node (ref "R204") (pin "2") (pinfunction "2_2") (pintype "passive"))
      (node (ref "U204") (pin "1") (pinfunction "RG_1") (pintype "passive"))
    )
    (net (code "47") (name "Net-(R205-Pad2)") (class "Default")
      (node (ref "R205") (pin "2") (pinfunction "2_2") (pintype "passive"))
      (node (ref "R207") (pin "1") (pinfunction "1_1") (pintype "passive"))
    )
    (net (code "48") (name "Net-(R206-Pad1)") (class "Default")
      (node (ref "R206") (pin "1") (pinfunction "1_1") (pintype "passive"))
      (node (ref "R207") (pin "2") (pinfunction "2_2") (pintype "passive"))
    )
    (net (code "49") (name "Net-(R206-Pad2)") (class "Default")
      (node (ref "R206") (pin "2") (pinfunction "2_2") (pintype "passive"))
      (node (ref "R212") (pin "2") (pinfunction "2_2") (pintype "passive"))
    )
    (net (code "50") (name "Net-(R212-Pad1)") (class "Default")
      (node (ref "R212") (pin "1") (pinfunction "1_1") (pintype "passive"))
      (node (ref "R213") (pin "2") (pinfunction "2_2") (pintype "passive"))
    )
    (net (code "51") (name "Net-(R215-Pad1)") (class "Default")
      (node (ref "R215") (pin "1") (pinfunction "1_1") (pintype "passive"))
      (node (ref "U205") (pin "8") (pinfunction "RG_8") (pintype "passive"))
    )
    (net (code "52") (name "Net-(R215-Pad2)") (class "Default")
      (node (ref "R215") (pin "2") (pinfunction "2_2") (pintype "passive"))
      (node (ref "U205") (pin "1") (pinfunction "RG_1") (pintype "passive"))
    )
    (net (code "53") (name "Net-(U101-C1)") (class "Default")
      (node (ref "C111") (pin "2") (pinfunction "2_2") (pintype "passive"))
      (node (ref "U101") (pin "20") (pinfunction "C1_20") (pintype "bidirectional"))
    )
    (net (code "54") (name "Net-(U101-C2)") (class "Default")
      (node (ref "C109") (pin "2") (pinfunction "2_2") (pintype "passive"))
      (node (ref "U101") (pin "21") (pinfunction "C2_21") (pintype "bidirectional"))
    )
    (net (code "55") (name "Net-(U102-C1)") (class "Default")
      (node (ref "C112") (pin "2") (pinfunction "2_2") (pintype "passive"))
      (node (ref "U102") (pin "20") (pinfunction "C1_20") (pintype "bidirectional"))
    )
    (net (code "56") (name "Net-(U102-C2)") (class "Default")
      (node (ref "C110") (pin "2") (pinfunction "2_2") (pintype "passive"))
      (node (ref "U102") (pin "21") (pinfunction "C2_21") (pintype "bidirectional"))
    )
    (net (code "57") (name "Net-(U105A--IN)") (class "Default")
      (node (ref "R113") (pin "2") (pinfunction "2_2") (pintype "passive"))
      (node (ref "R116") (pin "1") (pinfunction "1_1") (pintype "passive"))
      (node (ref "R117") (pin "1") (pinfunction "1_1") (pintype "passive"))
      (node (ref "U105") (pin "2") (pinfunction "-IN_2") (pintype "input"))
    )
    (net (code "58") (name "Net-(U105A-OUT)") (class "Default")
      (node (ref "R116") (pin "2") (pinfunction "2_2") (pintype "passive"))
      (node (ref "R117") (pin "2") (pinfunction "2_2") (pintype "passive"))
      (node (ref "R124") (pin "1") (pinfunction "1_1") (pintype "passive"))
      (node (ref "U105") (pin "1") (pinfunction "OUT_1") (pintype "output"))
    )
    (net (code "59") (name "Net-(U105B--IN)") (class "Default")
      (node (ref "R114") (pin "2") (pinfunction "2_2") (pintype "passive"))
      (node (ref "R118") (pin "1") (pinfunction "1_1") (pintype "passive"))
      (node (ref "R119") (pin "1") (pinfunction "1_1") (pintype "passive"))
      (node (ref "U105") (pin "6") (pinfunction "-IN_6") (pintype "input"))
    )
    (net (code "60") (name "Net-(U105B-OUT)") (class "Default")
      (node (ref "R118") (pin "2") (pinfunction "2_2") (pintype "passive"))
      (node (ref "R119") (pin "2") (pinfunction "2_2") (pintype "passive"))
      (node (ref "R125") (pin "1") (pinfunction "1_1") (pintype "passive"))
      (node (ref "U105") (pin "7") (pinfunction "OUT_7") (pintype "output"))
    )
    (net (code "61") (name "Net-(U105C--IN)") (class "Default")
      (node (ref "R125") (pin "2") (pinfunction "2_2") (pintype "passive"))
      (node (ref "R127") (pin "1") (pinfunction "1_1") (pintype "passive"))
      (node (ref "U105") (pin "11") (pinfunction "-IN_11") (pintype "input"))
    )
    (net (code "62") (name "Net-(U105D--IN)") (class "Default")
      (node (ref "R124") (pin "2") (pinfunction "2_2") (pintype "passive"))
      (node (ref "R126") (pin "1") (pinfunction "1_1") (pintype "passive"))
      (node (ref "U105") (pin "15") (pinfunction "-IN_15") (pintype "input"))
    )
    (net (code "63") (name "Net-(U201-OUT)") (class "Default")
      (node (ref "R208") (pin "1") (pinfunction "1_1") (pintype "passive"))
      (node (ref "U201") (pin "6") (pinfunction "OUT_6") (pintype "output"))
    )
    (net (code "64") (name "Net-(U202-OUT)") (class "Default")
      (node (ref "R209") (pin "1") (pinfunction "1_1") (pintype "passive"))
      (node (ref "U202") (pin "6") (pinfunction "OUT_6") (pintype "output"))
    )
    (net (code "65") (name "Net-(U203-OUT)") (class "Default")
      (node (ref "R210") (pin "1") (pinfunction "1_1") (pintype "passive"))
      (node (ref "U203") (pin "6") (pinfunction "OUT_6") (pintype "output"))
    )
    (net (code "66") (name "Net-(U204-OUT)") (class "Default")
      (node (ref "R211") (pin "1") (pinfunction "1_1") (pintype "passive"))
      (node (ref "U204") (pin "6") (pinfunction "OUT_6") (pintype "output"))
    )
    (net (code "67") (name "Net-(U205-+)") (class "Default")
      (node (ref "R213") (pin "1") (pinfunction "1_1") (pintype "passive"))
      (node (ref "R214") (pin "2") (pinfunction "2_2") (pintype "passive"))
      (node (ref "U205") (pin "3") (pinfunction "+_3") (pintype "input"))
    )
    (net (code "68") (name "Net-(U205-OUT)") (class "Default")
      (node (ref "R216") (pin "1") (pinfunction "1_1") (pintype "passive"))
      (node (ref "U205") (pin "6") (pinfunction "OUT_6") (pintype "output"))
    )
    (net (code "69") (name "Net-(U206-CH0)") (class "Default")
      (node (ref "C209") (pin "1") (pinfunction "1_1") (pintype "passive"))
      (node (ref "R208") (pin "2") (pinfunction "2_2") (pintype "passive"))
      (node (ref "U206") (pin "2") (pinfunction "CH0_2") (pintype "input"))
    )
    (net (code "70") (name "Net-(U206-CH1)") (class "Default")
      (node (ref "C210") (pin "1") (pinfunction "1_1") (pintype "passive"))
      (node (ref "R209") (pin "2") (pinfunction "2_2") (pintype "passive"))
      (node (ref "U206") (pin "3") (pinfunction "CH1_3") (pintype "input"))
    )
    (net (code "71") (name "Net-(U207-CH0)") (class "Default")
      (node (ref "C211") (pin "1") (pinfunction "1_1") (pintype "passive"))
      (node (ref "R210") (pin "2") (pinfunction "2_2") (pintype "passive"))
      (node (ref "U207") (pin "2") (pinfunction "CH0_2") (pintype "input"))
    )
    (net (code "72") (name "Net-(U207-CH1)") (class "Default")
      (node (ref "C212") (pin "1") (pinfunction "1_1") (pintype "passive"))
      (node (ref "R211") (pin "2") (pinfunction "2_2") (pintype "passive"))
      (node (ref "U207") (pin "3") (pinfunction "CH1_3") (pintype "input"))
    )
    (net (code "73") (name "Net-(U208-CH0)") (class "Default")
      (node (ref "C218") (pin "1") (pinfunction "1_1") (pintype "passive"))
      (node (ref "R216") (pin "2") (pinfunction "2_2") (pintype "passive"))
      (node (ref "U208") (pin "2") (pinfunction "CH0_2") (pintype "input"))
    )
    (net (code "74") (name "Net-(U208-CH1)") (class "Default")
      (node (ref "R217") (pin "2") (pinfunction "2_2") (pintype "passive"))
      (node (ref "U208") (pin "3") (pinfunction "CH1_3") (pintype "input"))
    )
    (net (code "75") (name "Net-(U301-BYP)") (class "Default")
      (node (ref "C310") (pin "1") (pinfunction "1_1") (pintype "passive"))
      (node (ref "U301") (pin "4") (pinfunction "BYP_4") (pintype "power_in"))
    )
    (net (code "76") (name "Net-(U302-CC+)") (class "Default")
      (node (ref "C307") (pin "2") (pinfunction "2_2") (pintype "passive"))
      (node (ref "U302") (pin "1") (pinfunction "CC+_1") (pintype "passive"))
    )
    (net (code "77") (name "Net-(U302-CC-)") (class "Default")
      (node (ref "C309") (pin "1") (pinfunction "1_1") (pintype "passive"))
      (node (ref "U302") (pin "8") (pinfunction "CC-_8") (pintype "passive"))
    )
    (net (code "78") (name "Net-(U302-LX+)") (class "Default")
      (node (ref "D301") (pin "A") (pinfunction "A_A") (pintype "passive"))
      (node (ref "L302") (pin "2") (pinfunction "2_2") (pintype "passive"))
      (node (ref "U302") (pin "15") (pinfunction "LX+_15") (pintype "passive"))
    )
    (net (code "79") (name "Net-(U302-LX-)") (class "Default")
      (node (ref "D302") (pin "C") (pinfunction "C_C") (pintype "passive"))
      (node (ref "L301") (pin "1") (pinfunction "1_1") (pintype "passive"))
      (node (ref "U302") (pin "10") (pinfunction "LX-_10") (pintype "passive"))
    )
    (net (code "80") (name "Net-(U302-SS)") (class "Default")
      (node (ref "C306") (pin "+") (pinfunction "+_+") (pintype "passive"))
      (node (ref "U302") (pin "7") (pinfunction "SS_7") (pintype "passive"))
    )
    (net (code "81") (name "Net-(U302-VREF)") (class "Default")
      (node (ref "C308") (pin "+") (pinfunction "+_+") (pintype "passive"))
      (node (ref "U302") (pin "6") (pinfunction "VREF_6") (pintype "power_in"))
    )
    (net (code "82") (name "Net-(U401-A1)") (class "Default")
      (node (ref "Q401") (pin "E") (pinfunction "E_E") (pintype "passive"))
      (node (ref "R401") (pin "1") (pinfunction "1_1") (pintype "passive"))
      (node (ref "U401") (pin "1") (pinfunction "A1_1") (pintype "input"))
    )
    (net (code "83") (name "Net-(U401-A2)") (class "Default")
      (node (ref "Q404") (pin "E") (pinfunction "E_E") (pintype "passive"))
      (node (ref "R402") (pin "1") (pinfunction "1_1") (pintype "passive"))
      (node (ref "U401") (pin "4") (pinfunction "A2_4") (pintype "input"))
    )
    (net (code "84") (name "Net-(U402-A1)") (class "Default")
      (node (ref "Q402") (pin "E") (pinfunction "E_E") (pintype "passive"))
      (node (ref "R403") (pin "1") (pinfunction "1_1") (pintype "passive"))
      (node (ref "U402") (pin "1") (pinfunction "A1_1") (pintype "input"))
    )
    (net (code "85") (name "Net-(U402-A2)") (class "Default")
      (node (ref "Q405") (pin "E") (pinfunction "E_E") (pintype "passive"))
      (node (ref "R405") (pin "1") (pinfunction "1_1") (pintype "passive"))
      (node (ref "U402") (pin "4") (pinfunction "A2_4") (pintype "input"))
    )
    (net (code "86") (name "Net-(U403-A1)") (class "Default")
      (node (ref "Q403") (pin "E") (pinfunction "E_E") (pintype "passive"))
      (node (ref "R404") (pin "1") (pinfunction "1_1") (pintype "passive"))
      (node (ref "U403") (pin "1") (pinfunction "A1_1") (pintype "input"))
    )
    (net (code "87") (name "Net-(U403-A2)") (class "Default")
      (node (ref "Q406") (pin "E") (pinfunction "E_E") (pintype "passive"))
      (node (ref "R406") (pin "1") (pinfunction "1_1") (pintype "passive"))
      (node (ref "U403") (pin "4") (pinfunction "A2_4") (pintype "input"))
    )
    (net (code "88") (name "Net-(U403-VO2)") (class "Default")
      (node (ref "C412") (pin "1") (pinfunction "1_1") (pintype "passive"))
      (node (ref "R412") (pin "1") (pinfunction "1_1") (pintype "passive"))
      (node (ref "U403") (pin "6") (pinfunction "VO2_6") (pintype "output"))
    )
    (net (code "89") (name "Net-(U404-A1)") (class "Default")
      (node (ref "Q407") (pin "E") (pinfunction "E_E") (pintype "passive"))
      (node (ref "R413") (pin "1") (pinfunction "1_1") (pintype "passive"))
      (node (ref "U404") (pin "1") (pinfunction "A1_1") (pintype "input"))
    )
    (net (code "90") (name "Net-(U404-A2)") (class "Default")
      (node (ref "Q408") (pin "E") (pinfunction "E_E") (pintype "passive"))
      (node (ref "R414") (pin "1") (pinfunction "1_1") (pintype "passive"))
      (node (ref "U404") (pin "4") (pinfunction "A2_4") (pintype "input"))
    )
    (net (code "91") (name "Net-(U405-A1)") (class "Default")
      (node (ref "Q409") (pin "E") (pinfunction "E_E") (pintype "passive"))
      (node (ref "R417") (pin "1") (pinfunction "1_1") (pintype "passive"))
      (node (ref "U405") (pin "1") (pinfunction "A1_1") (pintype "input"))
    )
    (net (code "92") (name "Net-(U405-A2)") (class "Default")
      (node (ref "Q411") (pin "E") (pinfunction "E_E") (pintype "passive"))
      (node (ref "R419") (pin "1") (pinfunction "1_1") (pintype "passive"))
      (node (ref "U405") (pin "4") (pinfunction "A2_4") (pintype "input"))
    )
    (net (code "93") (name "Net-(U406-A1)") (class "Default")
      (node (ref "Q410") (pin "E") (pinfunction "E_E") (pintype "passive"))
      (node (ref "R418") (pin "1") (pinfunction "1_1") (pintype "passive"))
      (node (ref "U406") (pin "1") (pinfunction "A1_1") (pintype "input"))
    )
    (net (code "94") (name "Net-(U406-A2)") (class "Default")
      (node (ref "Q412") (pin "E") (pinfunction "E_E") (pintype "passive"))
      (node (ref "R420") (pin "1") (pinfunction "1_1") (pintype "passive"))
      (node (ref "U406") (pin "4") (pinfunction "A2_4") (pintype "input"))
    )
    (net (code "95") (name "SCK") (class "Default")
      (node (ref "Q407") (pin "B") (pinfunction "B_B") (pintype "passive"))
    )
    (net (code "96") (name "SCK_I") (class "Default")
      (node (ref "C415") (pin "1") (pinfunction "1_1") (pintype "passive"))
      (node (ref "R415") (pin "1") (pinfunction "1_1") (pintype "passive"))
      (node (ref "U101") (pin "8") (pinfunction "SCK_8") (pintype "bidirectional"))
      (node (ref "U102") (pin "8") (pinfunction "SCK_8") (pintype "bidirectional"))
      (node (ref "U106") (pin "7") (pinfunction "SCK_7") (pintype "input"))
      (node (ref "U206") (pin "7") (pinfunction "SCK_7") (pintype "input"))
      (node (ref "U207") (pin "7") (pinfunction "SCK_7") (pintype "input"))
      (node (ref "U208") (pin "7") (pinfunction "SCK_7") (pintype "input"))
      (node (ref "U404") (pin "7") (pinfunction "VO1_7") (pintype "output"))
    )
    (net (code "97") (name "SDO_DAC1") (class "Default")
      (node (ref "U101") (pin "10") (pinfunction "SDO_10") (pintype "bidirectional"))
      (node (ref "U102") (pin "9") (pinfunction "SDI_9") (pintype "bidirectional"))
    )
    (net (code "98") (name "SDO_DAC2") (class "Default")
      (node (ref "U102") (pin "10") (pinfunction "SDO_10") (pintype "bidirectional"))
    )
    (net (code "99") (name "SS_CH") (class "Default")
      (node (ref "Q411") (pin "B") (pinfunction "B_B") (pintype "passive"))
    )
    (net (code "100") (name "SS_CH_I") (class "Default")
      (node (ref "C423") (pin "1") (pinfunction "1_1") (pintype "passive"))
      (node (ref "R423") (pin "1") (pinfunction "1_1") (pintype "passive"))
      (node (ref "U207") (pin "1") (pinfunction "CONV_1") (pintype "input"))
      (node (ref "U405") (pin "6") (pinfunction "VO2_6") (pintype "output"))
    )
    (net (code "101") (name "SS_CL") (class "Default")
      (node (ref "Q409") (pin "B") (pinfunction "B_B") (pintype "passive"))
    )
    (net (code "102") (name "SS_CL_I") (class "Default")
      (node (ref "C421") (pin "1") (pinfunction "1_1") (pintype "passive"))
      (node (ref "R421") (pin "1") (pinfunction "1_1") (pintype "passive"))
      (node (ref "U206") (pin "1") (pinfunction "CONV_1") (pintype "input"))
      (node (ref "U405") (pin "7") (pinfunction "VO1_7") (pintype "output"))
    )
    (net (code "103") (name "SS_DAC") (class "Default")
      (node (ref "Q404") (pin "B") (pinfunction "B_B") (pintype "passive"))
    )
    (net (code "104") (name "SS_DAC_I") (class "Default")
      (node (ref "C408") (pin "1") (pinfunction "1_1") (pintype "passive"))
      (node (ref "R408") (pin "1") (pinfunction "1_1") (pintype "passive"))
      (node (ref "U101") (pin "7") (pinfunction "LATCH_7") (pintype "bidirectional"))
      (node (ref "U102") (pin "7") (pinfunction "LATCH_7") (pintype "bidirectional"))
      (node (ref "U401") (pin "6") (pinfunction "VO2_6") (pintype "output"))
    )
    (net (code "105") (name "SS_TEMP") (class "Default")
      (node (ref "Q410") (pin "B") (pinfunction "B_B") (pintype "passive"))
    )
    (net (code "106") (name "SS_TEMP_I") (class "Default")
      (node (ref "C422") (pin "1") (pinfunction "1_1") (pintype "passive"))
      (node (ref "R422") (pin "1") (pinfunction "1_1") (pintype "passive"))
      (node (ref "U106") (pin "1") (pinfunction "CONV_1") (pintype "input"))
      (node (ref "U406") (pin "7") (pinfunction "VO1_7") (pintype "output"))
    )
    (net (code "107") (name "SS_V") (class "Default")
      (node (ref "Q412") (pin "B") (pinfunction "B_B") (pintype "passive"))
    )
    (net (code "108") (name "SS_V_I") (class "Default")
      (node (ref "C424") (pin "1") (pinfunction "1_1") (pintype "passive"))
      (node (ref "R424") (pin "1") (pinfunction "1_1") (pintype "passive"))
      (node (ref "U208") (pin "1") (pinfunction "CONV_1") (pintype "input"))
      (node (ref "U406") (pin "6") (pinfunction "VO2_6") (pintype "output"))
    )
    (net (code "109") (name "T1_OUT") (class "Default")
      (node (ref "C114") (pin "+") (pinfunction "+_+") (pintype "passive"))
      (node (ref "PAD611") (pin "1") (pinfunction "P_1") (pintype "passive"))
      (node (ref "PAD612") (pin "1") (pinfunction "P_1") (pintype "passive"))
      (node (ref "R120") (pin "1") (pinfunction "1_1") (pintype "passive"))
      (node (ref "U103") (pin "2") (pinfunction "VO_2") (pintype "output"))
    )
    (net (code "110") (name "T2_OUT") (class "Default")
      (node (ref "C115") (pin "+") (pinfunction "+_+") (pintype "passive"))
      (node (ref "PAD613") (pin "1") (pinfunction "P_1") (pintype "passive"))
      (node (ref "PAD614") (pin "1") (pinfunction "P_1") (pintype "passive"))
      (node (ref "R121") (pin "1") (pinfunction "1_1") (pintype "passive"))
      (node (ref "U104") (pin "2") (pinfunction "VO_2") (pintype "output"))
    )
    (net (code "111") (name "TEMP1") (class "Default")
      (node (ref "C116") (pin "1") (pinfunction "1_1") (pintype "passive"))
      (node (ref "R120") (pin "2") (pinfunction "2_2") (pintype "passive"))
      (node (ref "U106") (pin "2") (pinfunction "CH0_2") (pintype "input"))
    )
    (net (code "112") (name "TEMP2") (class "Default")
      (node (ref "C117") (pin "1") (pinfunction "1_1") (pintype "passive"))
      (node (ref "R121") (pin "2") (pinfunction "2_2") (pintype "passive"))
      (node (ref "U106") (pin "3") (pinfunction "CH1_3") (pintype "input"))
    )
    (net (code "113") (name "UUT+") (class "Default")
      (node (ref "Q1") (pin "2") (pinfunction "D_2") (pintype "passive"))
      (node (ref "Q2") (pin "2") (pinfunction "D_2") (pintype "passive"))
    )
    (net (code "114") (name "UUT-") (class "Default")
      (node (ref "PAD601") (pin "1") (pinfunction "P_1") (pintype "passive"))
      (node (ref "PAD602") (pin "1") (pinfunction "P_1") (pintype "passive"))
      (node (ref "R109") (pin "1") (pinfunction "1_1") (pintype "passive"))
      (node (ref "R111") (pin "1") (pinfunction "1_1") (pintype "passive"))
      (node (ref "R128") (pin "1") (pinfunction "1_1") (pintype "passive"))
      (node (ref "R132") (pin "1") (pinfunction "1_1") (pintype "passive"))
      (node (ref "U105") (pin "3") (pinfunction "+IN_3") (pintype "input"))
      (node (ref "U105") (pin "5") (pinfunction "+IN_5") (pintype "input"))
      (node (ref "U201") (pin "2") (pinfunction "-_2") (pintype "input"))
      (node (ref "U204") (pin "2") (pinfunction "-_2") (pintype "input"))
    )
    (net (code "115") (name "VREF") (class "Default")
      (node (ref "U101") (pin "14") (pinfunction "REF_OUT_14") (pintype "bidirectional"))
      (node (ref "U101") (pin "15") (pinfunction "REF_IN_15") (pintype "bidirectional"))
      (node (ref "U102") (pin "15") (pinfunction "REF_IN_15") (pintype "bidirectional"))
    )
    (net (code "116") (name "VSENSE+") (class "Default")
      (node (ref "MOV201") (pin "1") (pinfunction "1_1") (pintype "passive"))
      (node (ref "PAD615") (pin "1") (pinfunction "P_1") (pintype "passive"))
      (node (ref "PAD616") (pin "1") (pinfunction "P_1") (pintype "passive"))
      (node (ref "R205") (pin "1") (pinfunction "1_1") (pintype "passive"))
    )
    (net (code "117") (name "VSENSE-") (class "Default")
      (node (ref "MOV204") (pin "2") (pinfunction "2_2") (pintype "passive"))
      (node (ref "PAD617") (pin "1") (pinfunction "P_1") (pintype "passive"))
      (node (ref "PAD618") (pin "1") (pinfunction "P_1") (pintype "passive"))
      (node (ref "U205") (pin "2") (pinfunction "-_2") (pintype "input"))
    )
    (net (code "118") (name "unconnected-(Q406-PadB)") (class "Default")
      (node (ref "Q406") (pin "B") (pinfunction "B_B") (pintype "passive"))
    )
    (net (code "119") (name "unconnected-(U101-BST-Pad19)") (class "Default")
      (node (ref "U101") (pin "19") (pinfunction "BST_19") (pintype "bidirectional"))
    )
    (net (code "120") (name "unconnected-(U101-IOUT-Pad18)") (class "Default")
      (node (ref "U101") (pin "18") (pinfunction "IOUT_18") (pintype "bidirectional"))
    )
    (net (code "121") (name "unconnected-(U101-O_TRIM-Pad16)") (class "Default")
      (node (ref "U101") (pin "16") (pinfunction "O_TRIM_16") (pintype "bidirectional"))
    )
    (net (code "122") (name "unconnected-(U102-BST-Pad19)") (class "Default")
      (node (ref "U102") (pin "19") (pinfunction "BST_19") (pintype "bidirectional"))
    )
    (net (code "123") (name "unconnected-(U102-IOUT-Pad18)") (class "Default")
      (node (ref "U102") (pin "18") (pinfunction "IOUT_18") (pintype "bidirectional"))
    )
    (net (code "124") (name "unconnected-(U102-O_TRIM-Pad16)") (class "Default")
      (node (ref "U102") (pin "16") (pinfunction "O_TRIM_16") (pintype "bidirectional"))
    )
    (net (code "125") (name "unconnected-(U102-REF_OUT-Pad14)") (class "Default")
      (node (ref "U102") (pin "14") (pinfunction "REF_OUT_14") (pintype "bidirectional"))
    )
  )
)
